# sensor_002.net
KiCad netlist of a schematic drawn in EAGLE
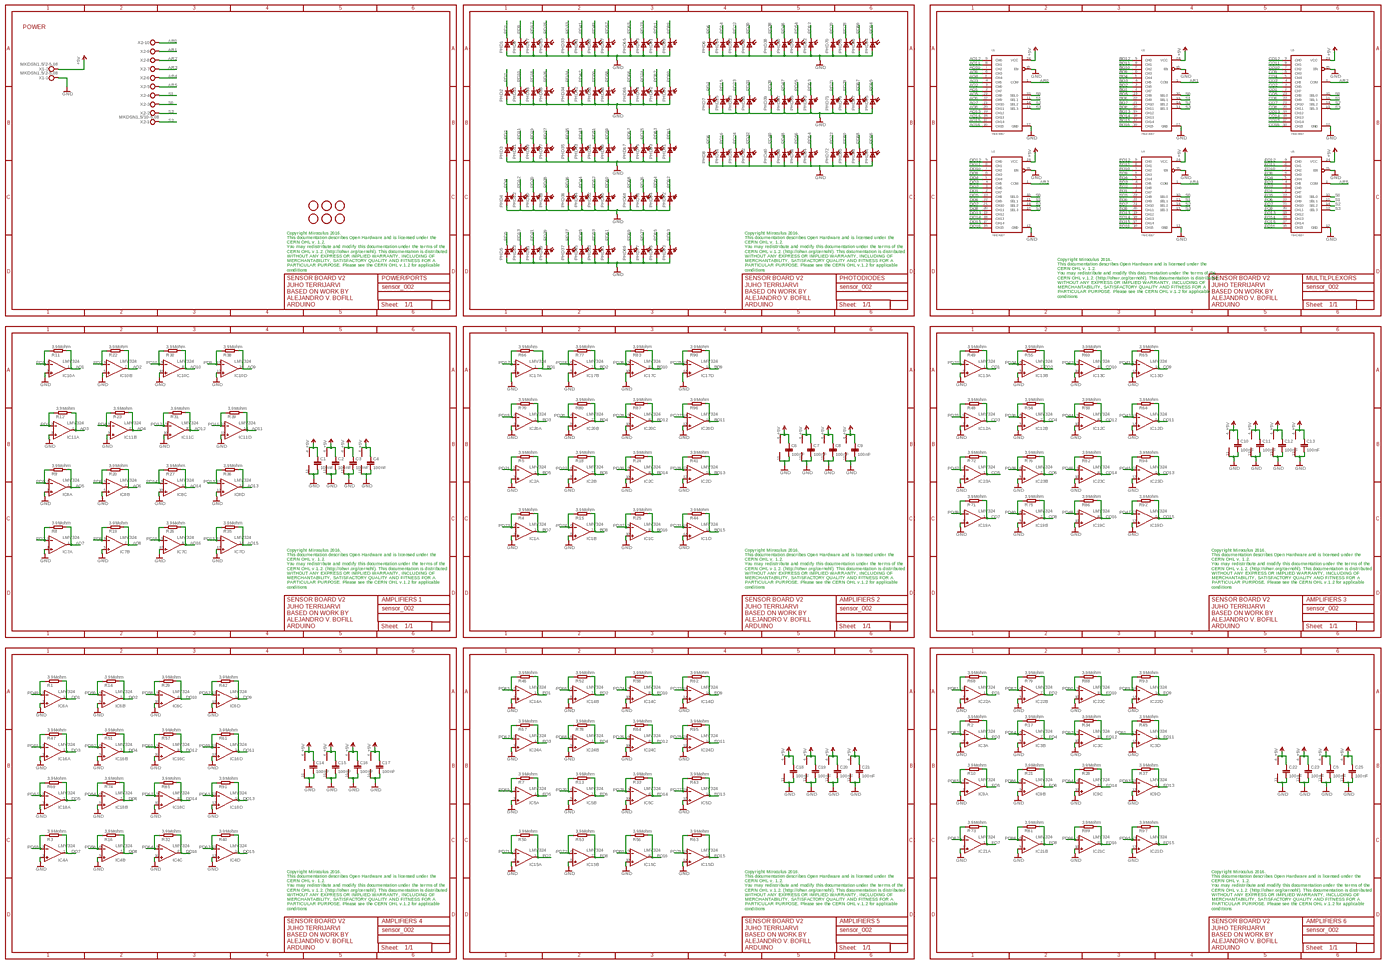
[diagram p0: schematic, sheet 1, overview]
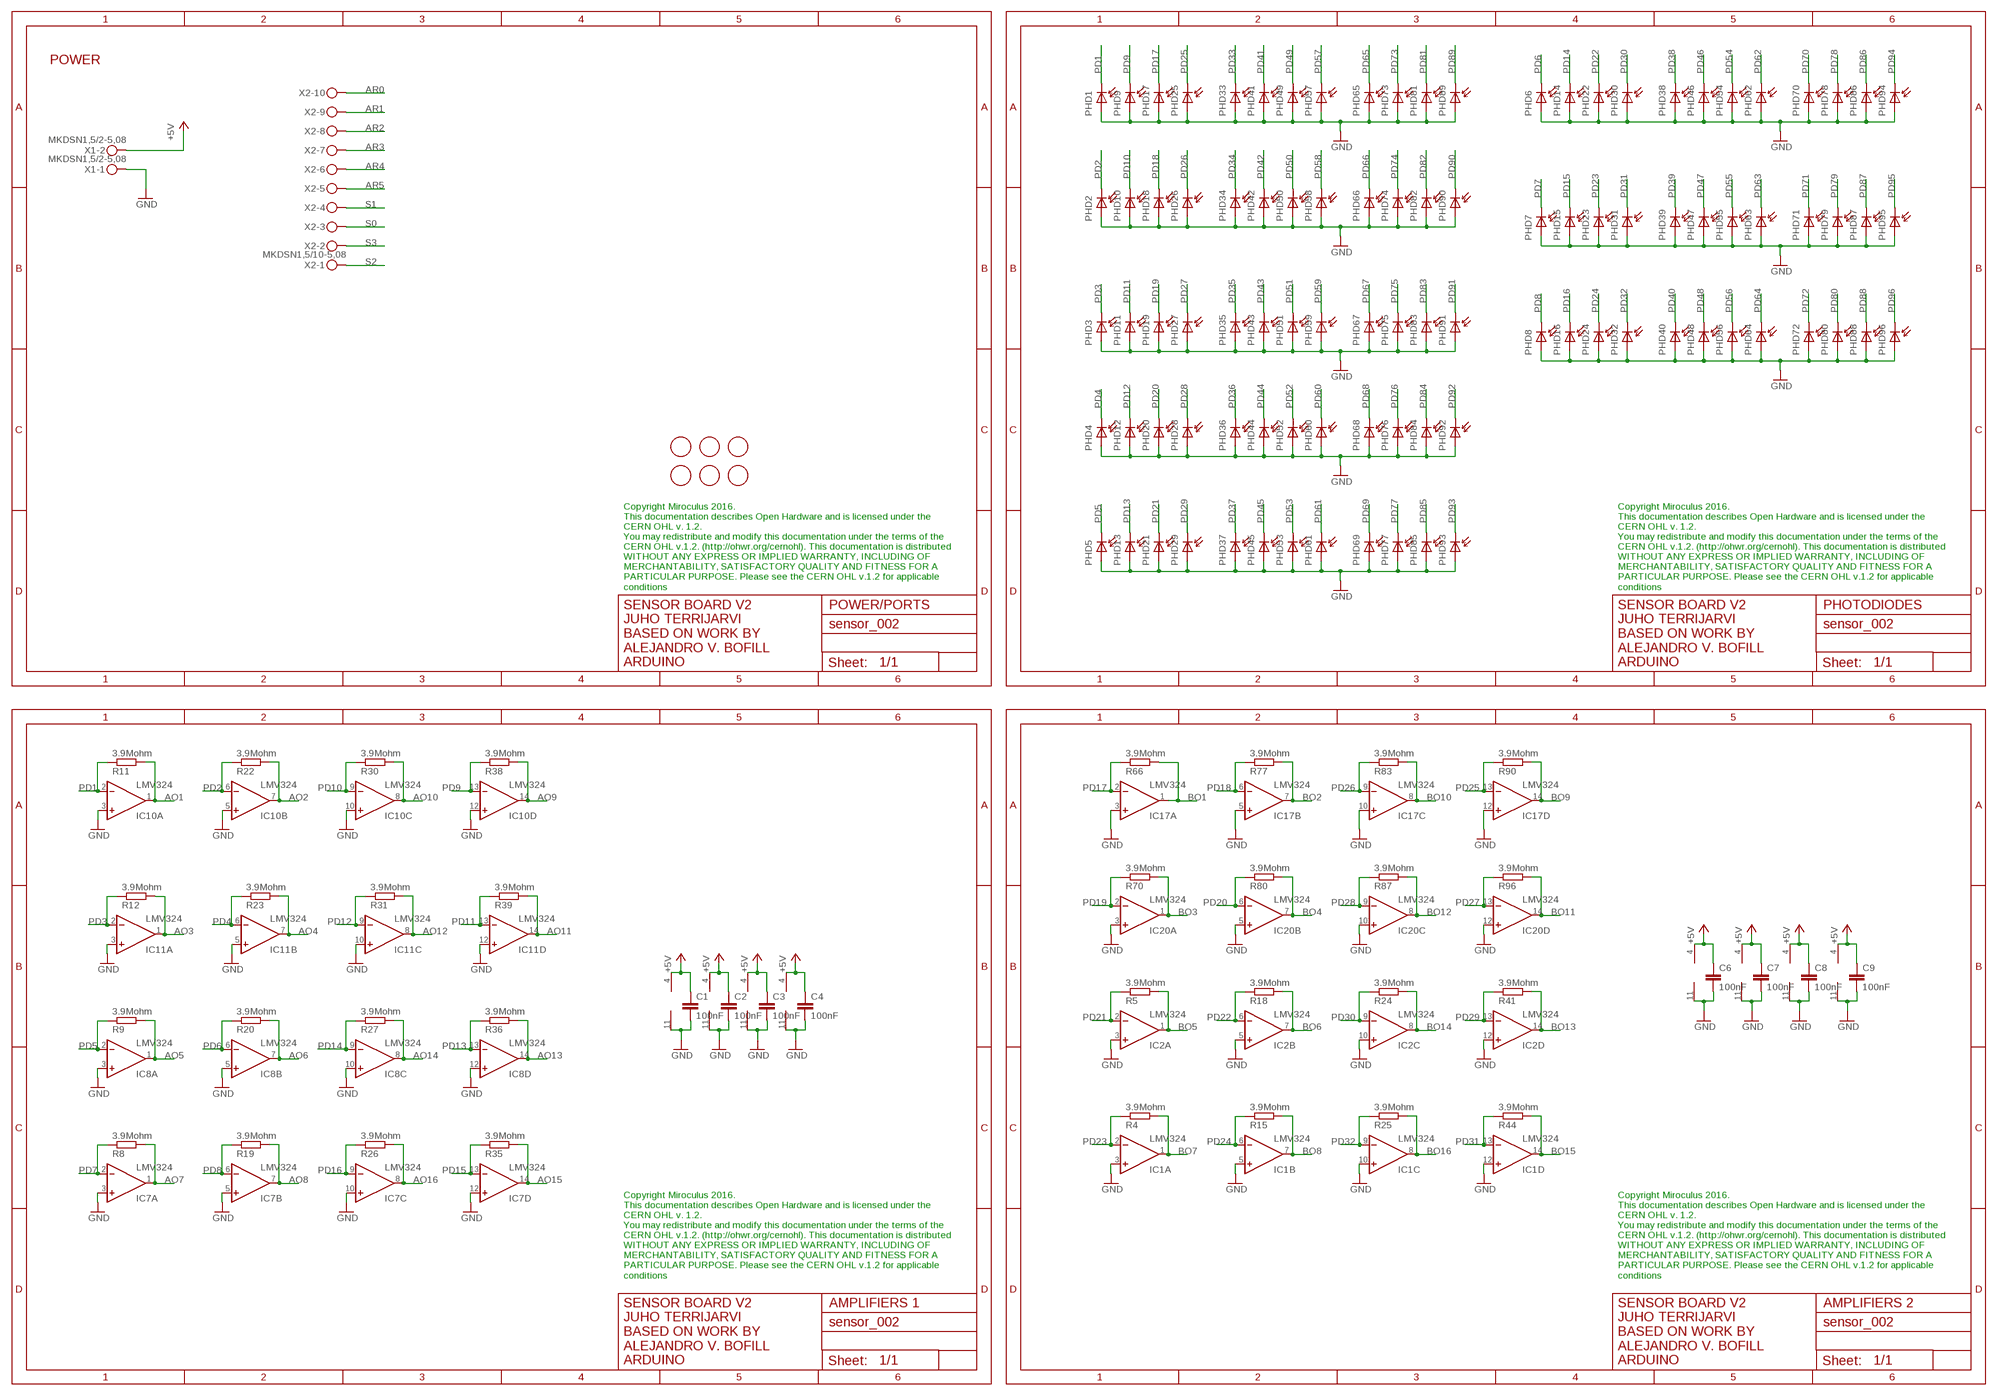
[diagram p1: schematic, sheet 1, part 1 of 4]
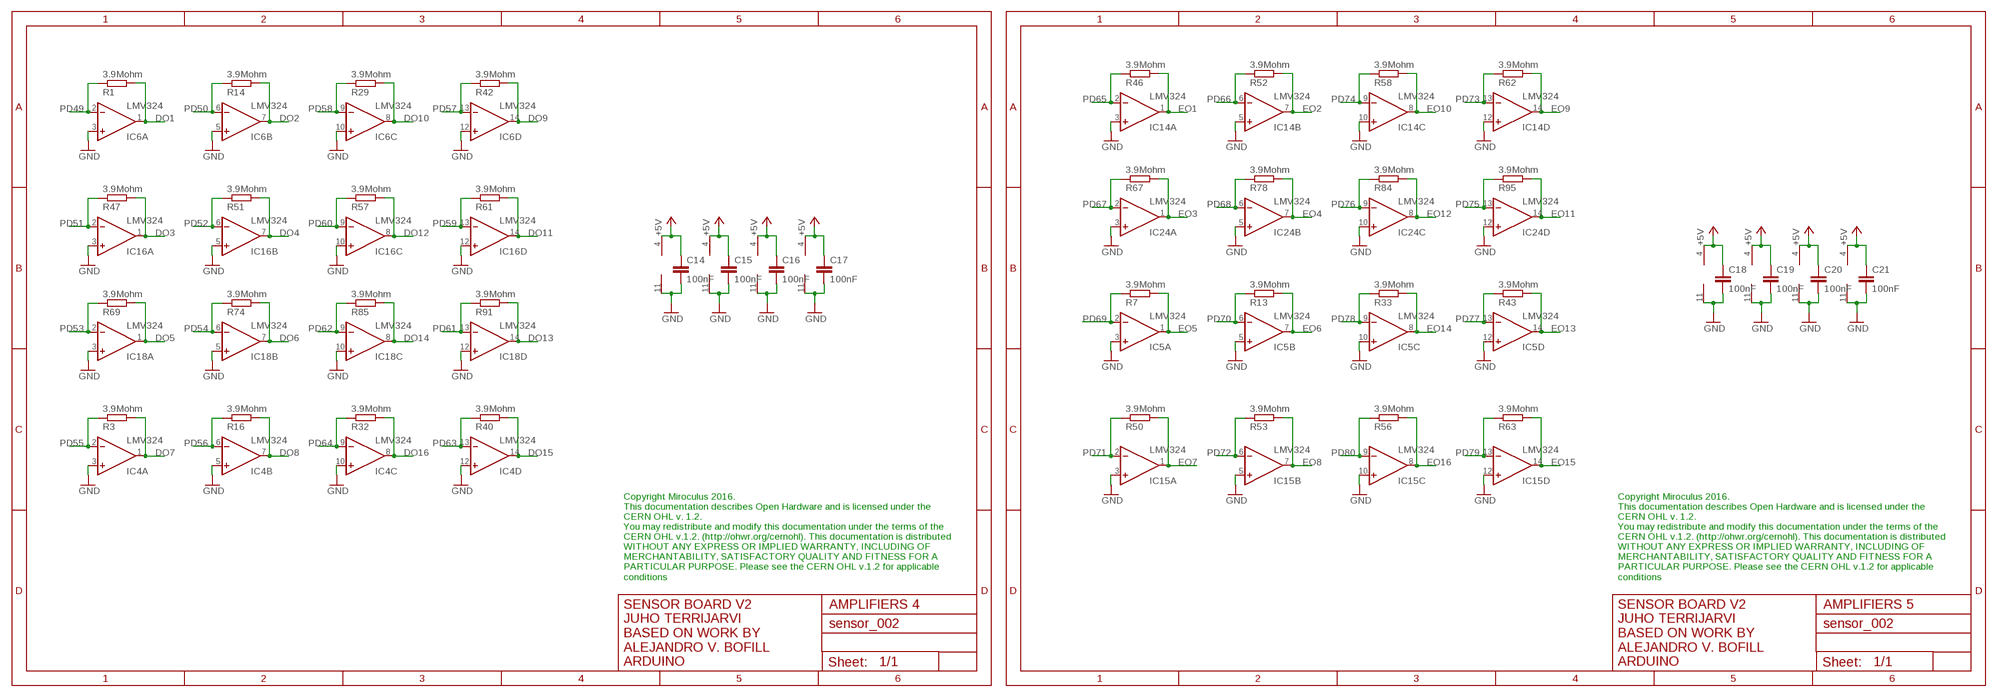
[diagram p2: schematic, sheet 1, part 2 of 4]
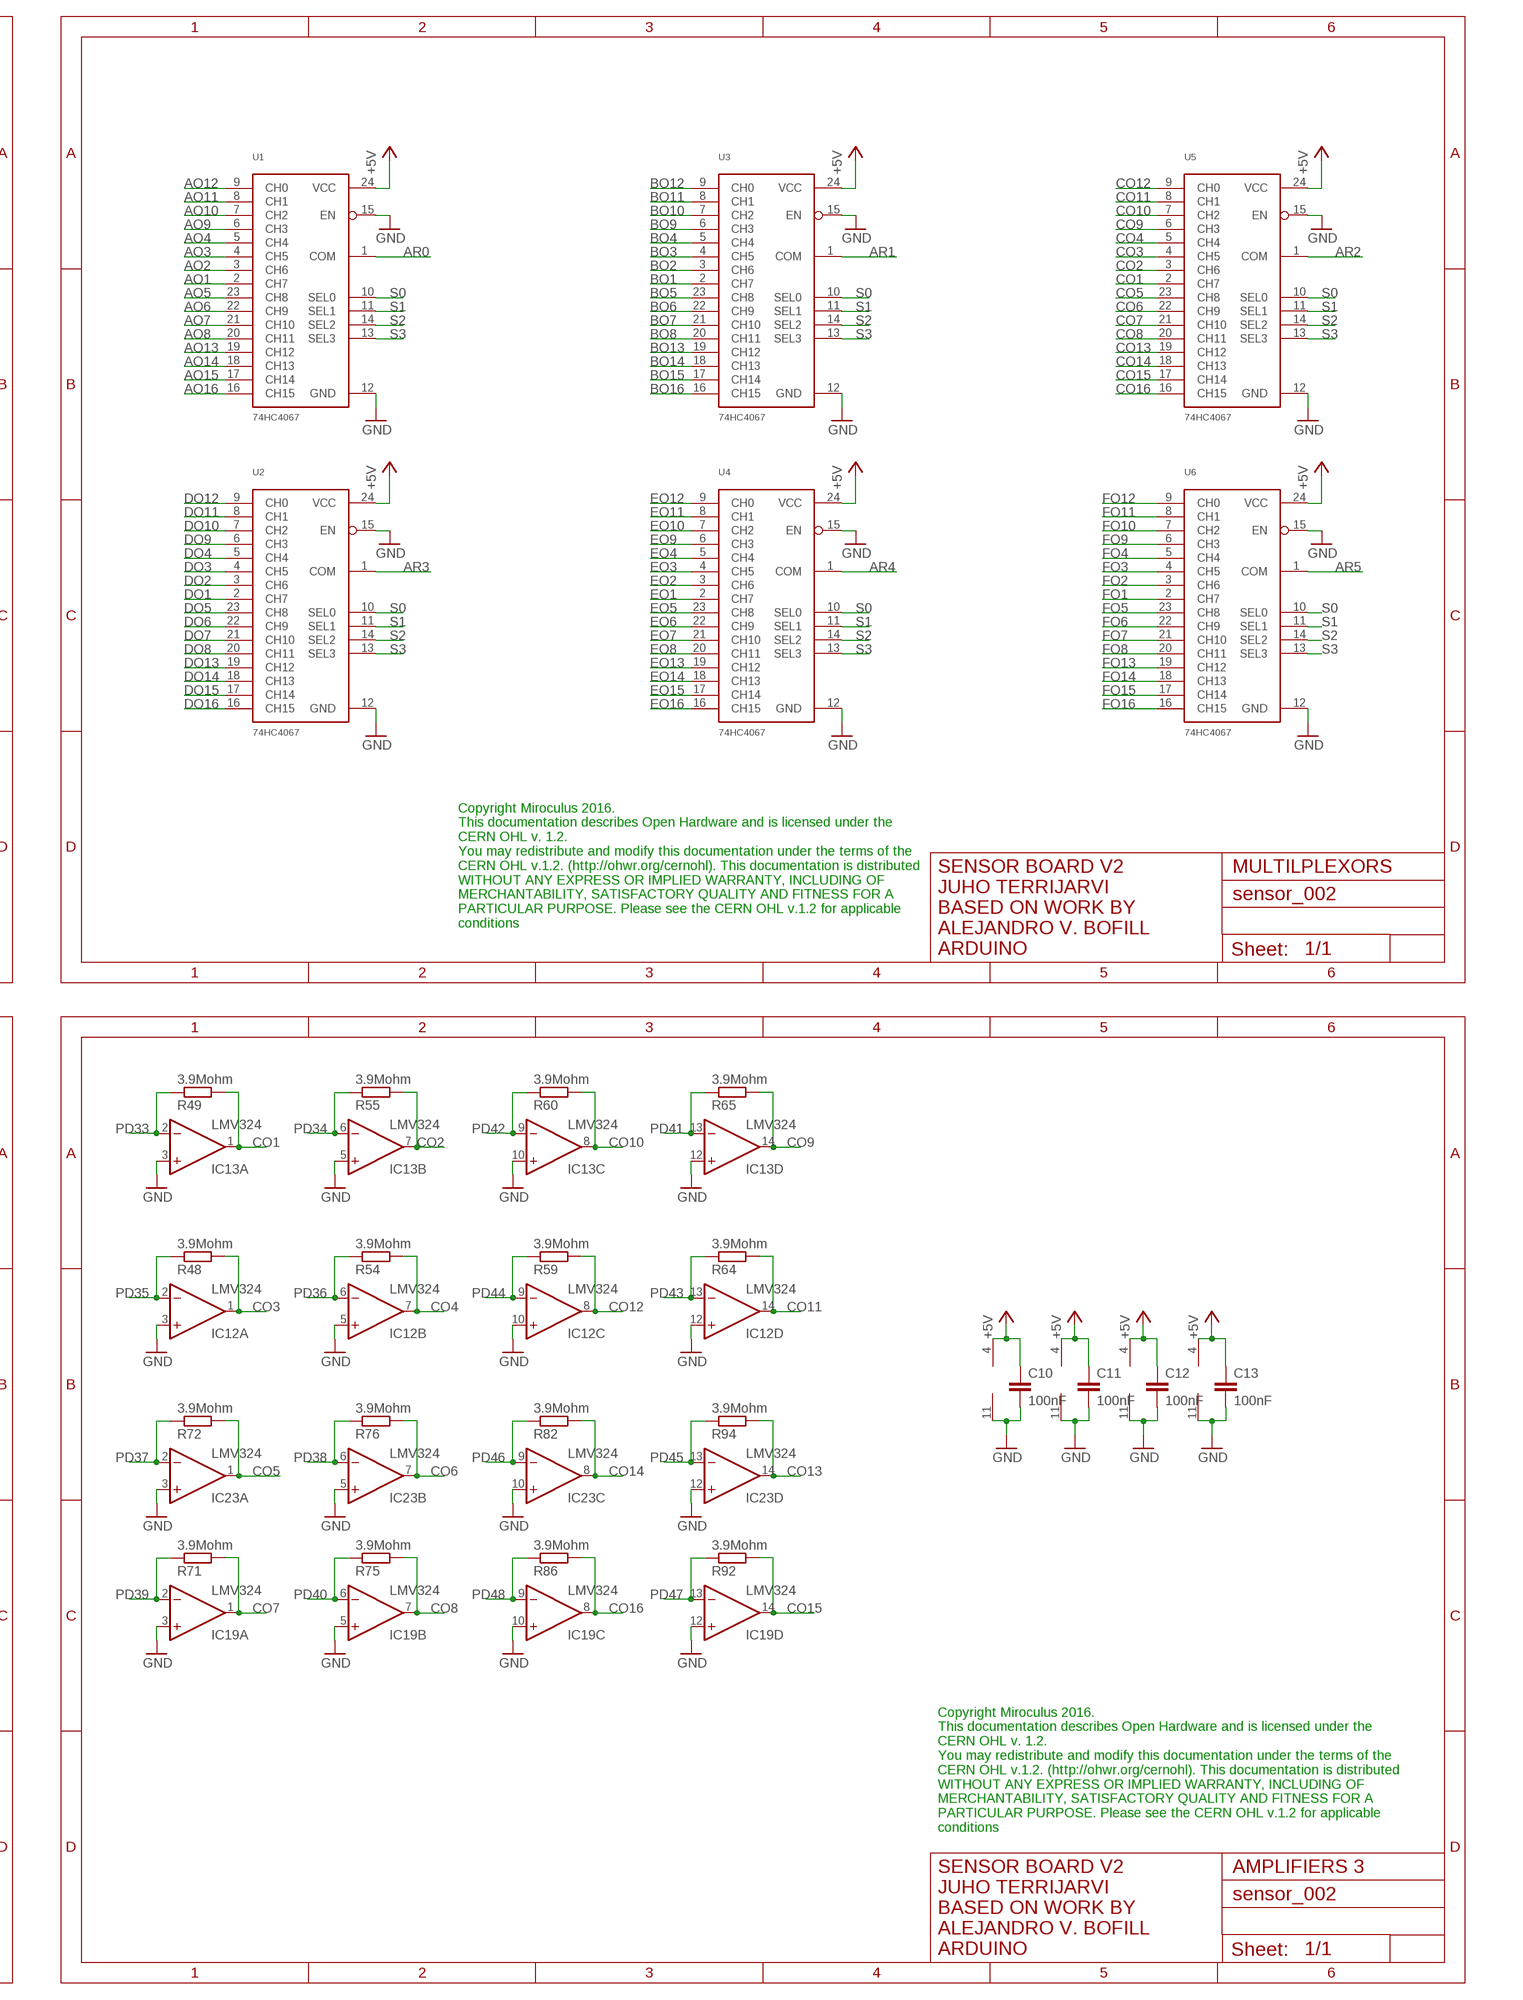
[diagram p3: schematic, sheet 1, part 3 of 4]
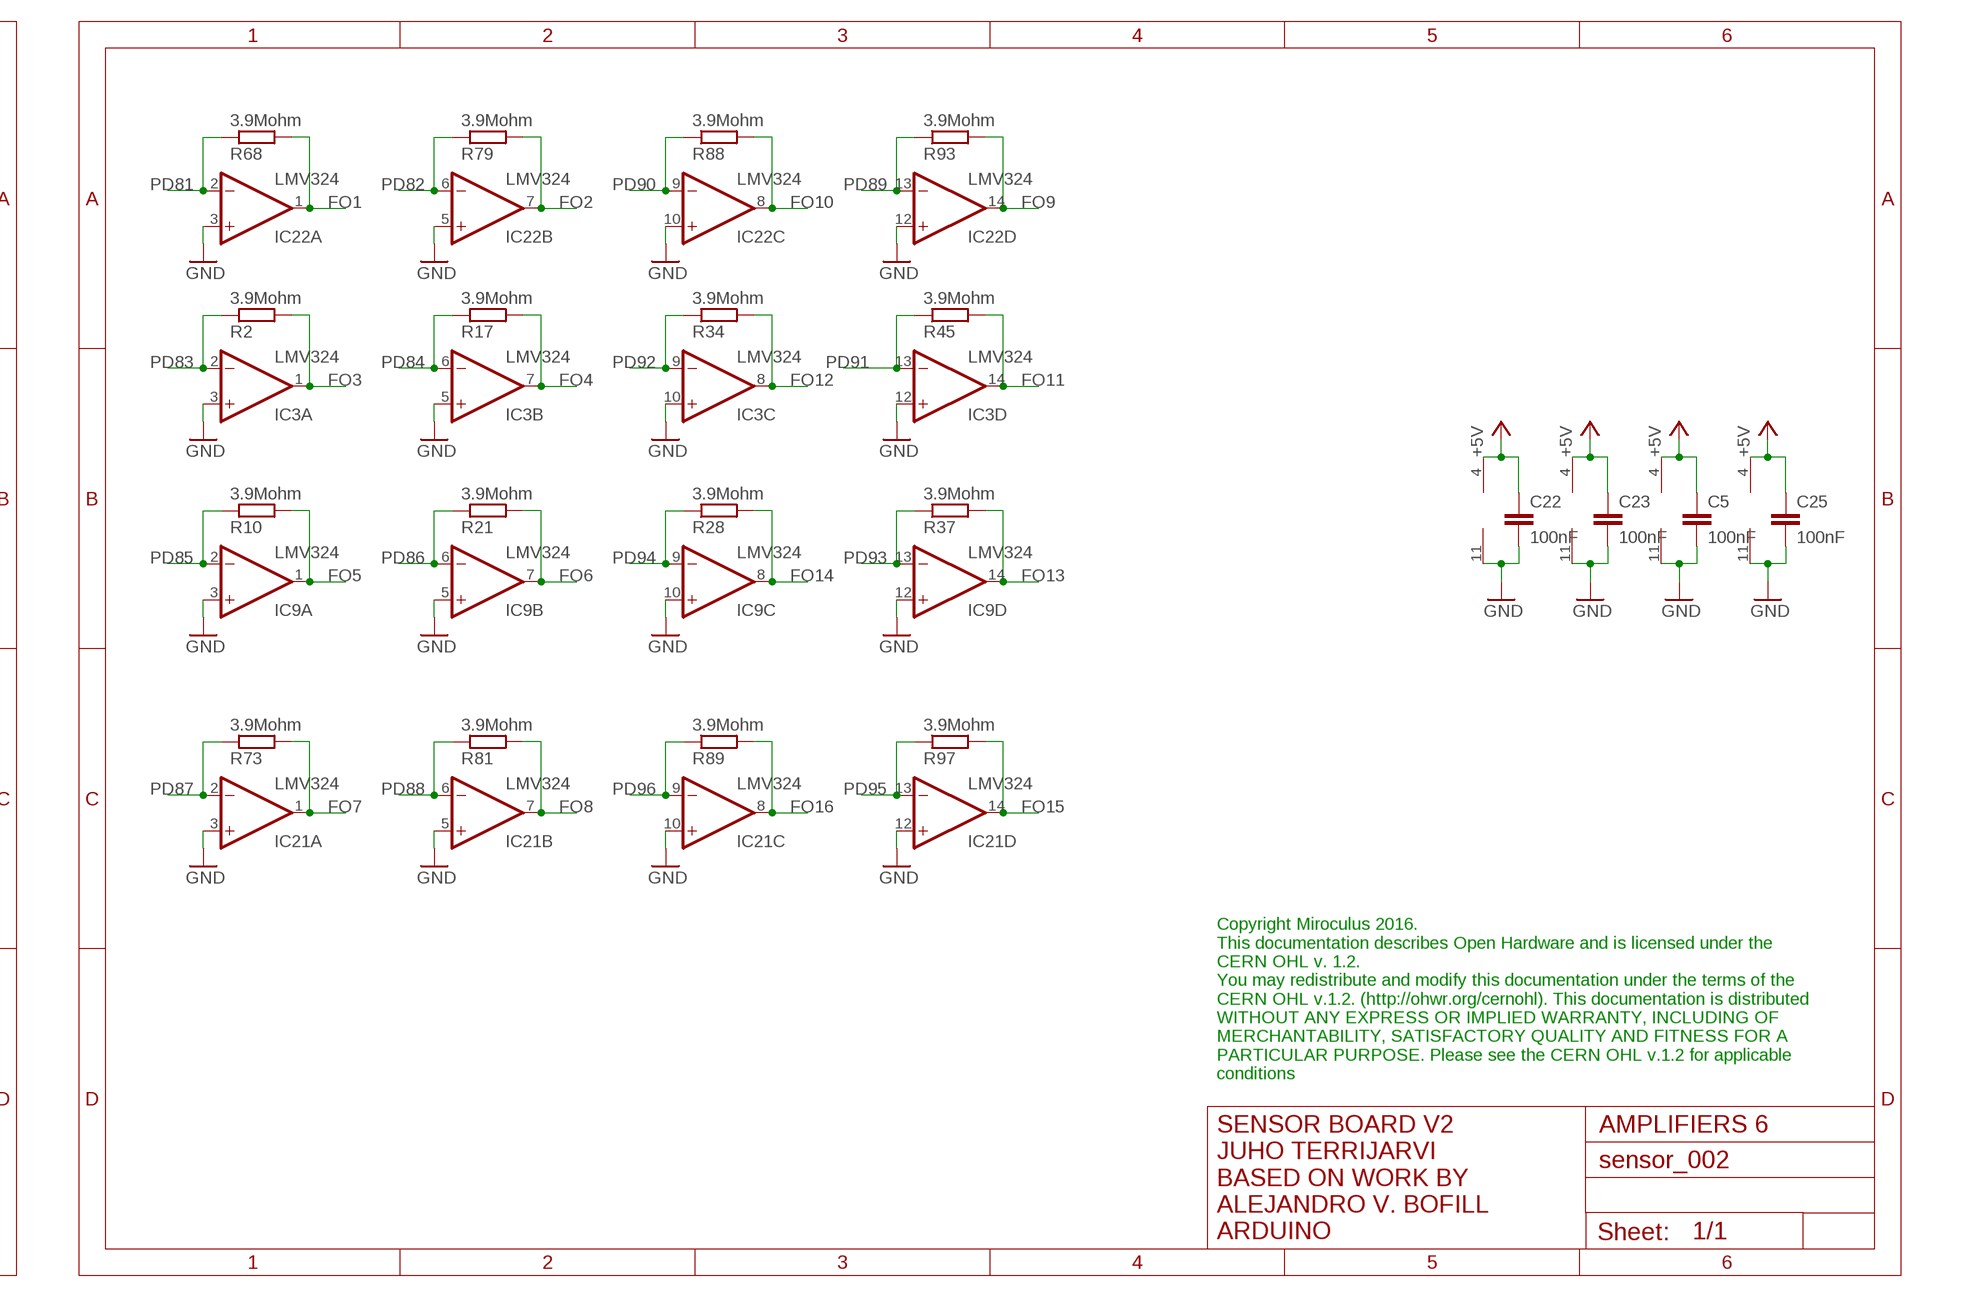
[diagram p4: schematic, sheet 1, part 4 of 4]

(export (version "E")
  (design (tool "Eeschema 10.0.6"))
  (components
    (comp (ref "C1")
      (value "100nF")
      (footprint "eagle-import:C0603")
      (libsource (lib "eagle-import") (part "C-EUC0603"))
    )
    (comp (ref "C2")
      (value "100nF")
      (footprint "eagle-import:C0603")
      (libsource (lib "eagle-import") (part "C-EUC0603"))
    )
    (comp (ref "C3")
      (value "100nF")
      (footprint "eagle-import:C0603")
      (libsource (lib "eagle-import") (part "C-EUC0603"))
    )
    (comp (ref "C4")
      (value "100nF")
      (footprint "eagle-import:C0603")
      (libsource (lib "eagle-import") (part "C-EUC0603"))
    )
    (comp (ref "C5")
      (value "100nF")
      (footprint "eagle-import:C0603")
      (libsource (lib "eagle-import") (part "C-EUC0603"))
    )
    (comp (ref "C6")
      (value "100nF")
      (footprint "eagle-import:C0603")
      (libsource (lib "eagle-import") (part "C-EUC0603"))
    )
    (comp (ref "C7")
      (value "100nF")
      (footprint "eagle-import:C0603")
      (libsource (lib "eagle-import") (part "C-EUC0603"))
    )
    (comp (ref "C8")
      (value "100nF")
      (footprint "eagle-import:C0603")
      (libsource (lib "eagle-import") (part "C-EUC0603"))
    )
    (comp (ref "C9")
      (value "100nF")
      (footprint "eagle-import:C0603")
      (libsource (lib "eagle-import") (part "C-EUC0603"))
    )
    (comp (ref "C10")
      (value "100nF")
      (footprint "eagle-import:C0603")
      (libsource (lib "eagle-import") (part "C-EUC0603"))
    )
    (comp (ref "C11")
      (value "100nF")
      (footprint "eagle-import:C0603")
      (libsource (lib "eagle-import") (part "C-EUC0603"))
    )
    (comp (ref "C12")
      (value "100nF")
      (footprint "eagle-import:C0603")
      (libsource (lib "eagle-import") (part "C-EUC0603"))
    )
    (comp (ref "C13")
      (value "100nF")
      (footprint "eagle-import:C0603")
      (libsource (lib "eagle-import") (part "C-EUC0603"))
    )
    (comp (ref "C14")
      (value "100nF")
      (footprint "eagle-import:C0603")
      (libsource (lib "eagle-import") (part "C-EUC0603"))
    )
    (comp (ref "C15")
      (value "100nF")
      (footprint "eagle-import:C0603")
      (libsource (lib "eagle-import") (part "C-EUC0603"))
    )
    (comp (ref "C16")
      (value "100nF")
      (footprint "eagle-import:C0603")
      (libsource (lib "eagle-import") (part "C-EUC0603"))
    )
    (comp (ref "C17")
      (value "100nF")
      (footprint "eagle-import:C0603")
      (libsource (lib "eagle-import") (part "C-EUC0603"))
    )
    (comp (ref "C18")
      (value "100nF")
      (footprint "eagle-import:C0603")
      (libsource (lib "eagle-import") (part "C-EUC0603"))
    )
    (comp (ref "C19")
      (value "100nF")
      (footprint "eagle-import:C0603")
      (libsource (lib "eagle-import") (part "C-EUC0603"))
    )
    (comp (ref "C20")
      (value "100nF")
      (footprint "eagle-import:C0603")
      (libsource (lib "eagle-import") (part "C-EUC0603"))
    )
    (comp (ref "C21")
      (value "100nF")
      (footprint "eagle-import:C0603")
      (libsource (lib "eagle-import") (part "C-EUC0603"))
    )
    (comp (ref "C22")
      (value "100nF")
      (footprint "eagle-import:C0603")
      (libsource (lib "eagle-import") (part "C-EUC0603"))
    )
    (comp (ref "C23")
      (value "100nF")
      (footprint "eagle-import:C0603")
      (libsource (lib "eagle-import") (part "C-EUC0603"))
    )
    (comp (ref "C25")
      (value "100nF")
      (footprint "eagle-import:C0603")
      (libsource (lib "eagle-import") (part "C-EUC0603"))
    )
    (comp (ref "FD1")
      (value "FIDUCIALMOUNT")
      (footprint "eagle-import:FIDUCIA-MOUNT")
      (libsource (lib "eagle-import") (part "FIDUCIALMOUNT"))
    )
    (comp (ref "FD2")
      (value "FIDUCIALMOUNT")
      (footprint "eagle-import:FIDUCIA-MOUNT")
      (libsource (lib "eagle-import") (part "FIDUCIALMOUNT"))
    )
    (comp (ref "FD3")
      (value "FIDUCIALMOUNT")
      (footprint "eagle-import:FIDUCIA-MOUNT")
      (libsource (lib "eagle-import") (part "FIDUCIALMOUNT"))
    )
    (comp (ref "FD4")
      (value "FIDUCIALMOUNT")
      (footprint "eagle-import:FIDUCIA-MOUNT")
      (libsource (lib "eagle-import") (part "FIDUCIALMOUNT"))
    )
    (comp (ref "FD5")
      (value "FIDUCIALMOUNT")
      (footprint "eagle-import:FIDUCIA-MOUNT")
      (libsource (lib "eagle-import") (part "FIDUCIALMOUNT"))
    )
    (comp (ref "FD6")
      (value "FIDUCIALMOUNT")
      (footprint "eagle-import:FIDUCIA-MOUNT")
      (libsource (lib "eagle-import") (part "FIDUCIALMOUNT"))
    )
    (comp (ref "IC1")
      (value "LMV324")
      (footprint "eagle-import:SO14")
      (libsource (lib "eagle-import") (part "TL074D"))
    )
    (comp (ref "IC2")
      (value "LMV324")
      (footprint "eagle-import:SO14")
      (libsource (lib "eagle-import") (part "TL074D"))
    )
    (comp (ref "IC3")
      (value "LMV324")
      (footprint "eagle-import:SO14")
      (libsource (lib "eagle-import") (part "TL074D"))
    )
    (comp (ref "IC4")
      (value "LMV324")
      (footprint "eagle-import:SO14")
      (libsource (lib "eagle-import") (part "TL074D"))
    )
    (comp (ref "IC5")
      (value "LMV324")
      (footprint "eagle-import:SO14")
      (libsource (lib "eagle-import") (part "TL074D"))
    )
    (comp (ref "IC6")
      (value "LMV324")
      (footprint "eagle-import:SO14")
      (libsource (lib "eagle-import") (part "TL074D"))
    )
    (comp (ref "IC7")
      (value "LMV324")
      (footprint "eagle-import:SO14")
      (libsource (lib "eagle-import") (part "TL074D"))
    )
    (comp (ref "IC8")
      (value "LMV324")
      (footprint "eagle-import:SO14")
      (libsource (lib "eagle-import") (part "TL074D"))
    )
    (comp (ref "IC9")
      (value "LMV324")
      (footprint "eagle-import:SO14")
      (libsource (lib "eagle-import") (part "TL074D"))
    )
    (comp (ref "IC10")
      (value "LMV324")
      (footprint "eagle-import:SO14")
      (libsource (lib "eagle-import") (part "TL074D"))
    )
    (comp (ref "IC11")
      (value "LMV324")
      (footprint "eagle-import:SO14")
      (libsource (lib "eagle-import") (part "TL074D"))
    )
    (comp (ref "IC12")
      (value "LMV324")
      (footprint "eagle-import:SO14")
      (libsource (lib "eagle-import") (part "TL074D"))
    )
    (comp (ref "IC13")
      (value "LMV324")
      (footprint "eagle-import:SO14")
      (libsource (lib "eagle-import") (part "TL074D"))
    )
    (comp (ref "IC14")
      (value "LMV324")
      (footprint "eagle-import:SO14")
      (libsource (lib "eagle-import") (part "TL074D"))
    )
    (comp (ref "IC15")
      (value "LMV324")
      (footprint "eagle-import:SO14")
      (libsource (lib "eagle-import") (part "TL074D"))
    )
    (comp (ref "IC16")
      (value "LMV324")
      (footprint "eagle-import:SO14")
      (libsource (lib "eagle-import") (part "TL074D"))
    )
    (comp (ref "IC17")
      (value "LMV324")
      (footprint "eagle-import:SO14")
      (libsource (lib "eagle-import") (part "TL074D"))
    )
    (comp (ref "IC18")
      (value "LMV324")
      (footprint "eagle-import:SO14")
      (libsource (lib "eagle-import") (part "TL074D"))
    )
    (comp (ref "IC19")
      (value "LMV324")
      (footprint "eagle-import:SO14")
      (libsource (lib "eagle-import") (part "TL074D"))
    )
    (comp (ref "IC20")
      (value "LMV324")
      (footprint "eagle-import:SO14")
      (libsource (lib "eagle-import") (part "TL074D"))
    )
    (comp (ref "IC21")
      (value "LMV324")
      (footprint "eagle-import:SO14")
      (libsource (lib "eagle-import") (part "TL074D"))
    )
    (comp (ref "IC22")
      (value "LMV324")
      (footprint "eagle-import:SO14")
      (libsource (lib "eagle-import") (part "TL074D"))
    )
    (comp (ref "IC23")
      (value "LMV324")
      (footprint "eagle-import:SO14")
      (libsource (lib "eagle-import") (part "TL074D"))
    )
    (comp (ref "IC24")
      (value "LMV324")
      (footprint "eagle-import:SO14")
      (libsource (lib "eagle-import") (part "TL074D"))
    )
    (comp (ref "PHD1")
      (value "CLS15-22C/L213G/TR8")
      (footprint "eagle-import:PD_0.2")
      (libsource (lib "eagle-import") (part "PD_0.2"))
    )
    (comp (ref "PHD2")
      (value "CLS15-22C/L213G/TR8")
      (footprint "eagle-import:PD_0.2")
      (libsource (lib "eagle-import") (part "PD_0.2"))
    )
    (comp (ref "PHD3")
      (value "CLS15-22C/L213G/TR8")
      (footprint "eagle-import:PD_0.2")
      (libsource (lib "eagle-import") (part "PD_0.2"))
    )
    (comp (ref "PHD4")
      (value "CLS15-22C/L213G/TR8")
      (footprint "eagle-import:PD_0.2")
      (libsource (lib "eagle-import") (part "PD_0.2"))
    )
    (comp (ref "PHD5")
      (value "CLS15-22C/L213G/TR8")
      (footprint "eagle-import:PD_0.2")
      (libsource (lib "eagle-import") (part "PD_0.2"))
    )
    (comp (ref "PHD6")
      (value "CLS15-22C/L213G/TR8")
      (footprint "eagle-import:PD_0.2")
      (libsource (lib "eagle-import") (part "PD_0.2"))
    )
    (comp (ref "PHD7")
      (value "CLS15-22C/L213G/TR8")
      (footprint "eagle-import:PD_0.2")
      (libsource (lib "eagle-import") (part "PD_0.2"))
    )
    (comp (ref "PHD8")
      (value "CLS15-22C/L213G/TR8")
      (footprint "eagle-import:PD_0.2")
      (libsource (lib "eagle-import") (part "PD_0.2"))
    )
    (comp (ref "PHD9")
      (value "CLS15-22C/L213G/TR8")
      (footprint "eagle-import:PD_0.2")
      (libsource (lib "eagle-import") (part "PD_0.2"))
    )
    (comp (ref "PHD10")
      (value "CLS15-22C/L213G/TR8")
      (footprint "eagle-import:PD_0.2")
      (libsource (lib "eagle-import") (part "PD_0.2"))
    )
    (comp (ref "PHD11")
      (value "CLS15-22C/L213G/TR8")
      (footprint "eagle-import:PD_0.2")
      (libsource (lib "eagle-import") (part "PD_0.2"))
    )
    (comp (ref "PHD12")
      (value "CLS15-22C/L213G/TR8")
      (footprint "eagle-import:PD_0.2")
      (libsource (lib "eagle-import") (part "PD_0.2"))
    )
    (comp (ref "PHD13")
      (value "CLS15-22C/L213G/TR8")
      (footprint "eagle-import:PD_0.2")
      (libsource (lib "eagle-import") (part "PD_0.2"))
    )
    (comp (ref "PHD14")
      (value "CLS15-22C/L213G/TR8")
      (footprint "eagle-import:PD_0.2")
      (libsource (lib "eagle-import") (part "PD_0.2"))
    )
    (comp (ref "PHD15")
      (value "CLS15-22C/L213G/TR8")
      (footprint "eagle-import:PD_0.2")
      (libsource (lib "eagle-import") (part "PD_0.2"))
    )
    (comp (ref "PHD16")
      (value "CLS15-22C/L213G/TR8")
      (footprint "eagle-import:PD_0.2")
      (libsource (lib "eagle-import") (part "PD_0.2"))
    )
    (comp (ref "PHD17")
      (value "CLS15-22C/L213G/TR8")
      (footprint "eagle-import:PD_0.2")
      (libsource (lib "eagle-import") (part "PD_0.2"))
    )
    (comp (ref "PHD18")
      (value "CLS15-22C/L213G/TR8")
      (footprint "eagle-import:PD_0.2")
      (libsource (lib "eagle-import") (part "PD_0.2"))
    )
    (comp (ref "PHD19")
      (value "CLS15-22C/L213G/TR8")
      (footprint "eagle-import:PD_0.2")
      (libsource (lib "eagle-import") (part "PD_0.2"))
    )
    (comp (ref "PHD20")
      (value "CLS15-22C/L213G/TR8")
      (footprint "eagle-import:PD_0.2")
      (libsource (lib "eagle-import") (part "PD_0.2"))
    )
    (comp (ref "PHD21")
      (value "CLS15-22C/L213G/TR8")
      (footprint "eagle-import:PD_0.2")
      (libsource (lib "eagle-import") (part "PD_0.2"))
    )
    (comp (ref "PHD22")
      (value "CLS15-22C/L213G/TR8")
      (footprint "eagle-import:PD_0.2")
      (libsource (lib "eagle-import") (part "PD_0.2"))
    )
    (comp (ref "PHD23")
      (value "CLS15-22C/L213G/TR8")
      (footprint "eagle-import:PD_0.2")
      (libsource (lib "eagle-import") (part "PD_0.2"))
    )
    (comp (ref "PHD24")
      (value "CLS15-22C/L213G/TR8")
      (footprint "eagle-import:PD_0.2")
      (libsource (lib "eagle-import") (part "PD_0.2"))
    )
    (comp (ref "PHD25")
      (value "CLS15-22C/L213G/TR8")
      (footprint "eagle-import:PD_0.2")
      (libsource (lib "eagle-import") (part "PD_0.2"))
    )
    (comp (ref "PHD26")
      (value "CLS15-22C/L213G/TR8")
      (footprint "eagle-import:PD_0.2")
      (libsource (lib "eagle-import") (part "PD_0.2"))
    )
    (comp (ref "PHD27")
      (value "CLS15-22C/L213G/TR8")
      (footprint "eagle-import:PD_0.2")
      (libsource (lib "eagle-import") (part "PD_0.2"))
    )
    (comp (ref "PHD28")
      (value "CLS15-22C/L213G/TR8")
      (footprint "eagle-import:PD_0.2")
      (libsource (lib "eagle-import") (part "PD_0.2"))
    )
    (comp (ref "PHD29")
      (value "CLS15-22C/L213G/TR8")
      (footprint "eagle-import:PD_0.2")
      (libsource (lib "eagle-import") (part "PD_0.2"))
    )
    (comp (ref "PHD30")
      (value "CLS15-22C/L213G/TR8")
      (footprint "eagle-import:PD_0.2")
      (libsource (lib "eagle-import") (part "PD_0.2"))
    )
    (comp (ref "PHD31")
      (value "CLS15-22C/L213G/TR8")
      (footprint "eagle-import:PD_0.2")
      (libsource (lib "eagle-import") (part "PD_0.2"))
    )
    (comp (ref "PHD32")
      (value "CLS15-22C/L213G/TR8")
      (footprint "eagle-import:PD_0.2")
      (libsource (lib "eagle-import") (part "PD_0.2"))
    )
    (comp (ref "PHD33")
      (value "CLS15-22C/L213G/TR8")
      (footprint "eagle-import:PD_0.2")
      (libsource (lib "eagle-import") (part "PD_0.2"))
    )
    (comp (ref "PHD34")
      (value "CLS15-22C/L213G/TR8")
      (footprint "eagle-import:PD_0.2")
      (libsource (lib "eagle-import") (part "PD_0.2"))
    )
    (comp (ref "PHD35")
      (value "CLS15-22C/L213G/TR8")
      (footprint "eagle-import:PD_0.2")
      (libsource (lib "eagle-import") (part "PD_0.2"))
    )
    (comp (ref "PHD36")
      (value "CLS15-22C/L213G/TR8")
      (footprint "eagle-import:PD_0.2")
      (libsource (lib "eagle-import") (part "PD_0.2"))
    )
    (comp (ref "PHD37")
      (value "CLS15-22C/L213G/TR8")
      (footprint "eagle-import:PD_0.2")
      (libsource (lib "eagle-import") (part "PD_0.2"))
    )
    (comp (ref "PHD38")
      (value "CLS15-22C/L213G/TR8")
      (footprint "eagle-import:PD_0.2")
      (libsource (lib "eagle-import") (part "PD_0.2"))
    )
    (comp (ref "PHD39")
      (value "CLS15-22C/L213G/TR8")
      (footprint "eagle-import:PD_0.2")
      (libsource (lib "eagle-import") (part "PD_0.2"))
    )
    (comp (ref "PHD40")
      (value "CLS15-22C/L213G/TR8")
      (footprint "eagle-import:PD_0.2")
      (libsource (lib "eagle-import") (part "PD_0.2"))
    )
    (comp (ref "PHD41")
      (value "CLS15-22C/L213G/TR8")
      (footprint "eagle-import:PD_0.2")
      (libsource (lib "eagle-import") (part "PD_0.2"))
    )
    (comp (ref "PHD42")
      (value "CLS15-22C/L213G/TR8")
      (footprint "eagle-import:PD_0.2")
      (libsource (lib "eagle-import") (part "PD_0.2"))
    )
    (comp (ref "PHD43")
      (value "CLS15-22C/L213G/TR8")
      (footprint "eagle-import:PD_0.2")
      (libsource (lib "eagle-import") (part "PD_0.2"))
    )
    (comp (ref "PHD44")
      (value "CLS15-22C/L213G/TR8")
      (footprint "eagle-import:PD_0.2")
      (libsource (lib "eagle-import") (part "PD_0.2"))
    )
    (comp (ref "PHD45")
      (value "CLS15-22C/L213G/TR8")
      (footprint "eagle-import:PD_0.2")
      (libsource (lib "eagle-import") (part "PD_0.2"))
    )
    (comp (ref "PHD46")
      (value "CLS15-22C/L213G/TR8")
      (footprint "eagle-import:PD_0.2")
      (libsource (lib "eagle-import") (part "PD_0.2"))
    )
    (comp (ref "PHD47")
      (value "CLS15-22C/L213G/TR8")
      (footprint "eagle-import:PD_0.2")
      (libsource (lib "eagle-import") (part "PD_0.2"))
    )
    (comp (ref "PHD48")
      (value "CLS15-22C/L213G/TR8")
      (footprint "eagle-import:PD_0.2")
      (libsource (lib "eagle-import") (part "PD_0.2"))
    )
    (comp (ref "PHD49")
      (value "CLS15-22C/L213G/TR8")
      (footprint "eagle-import:PD_0.2")
      (libsource (lib "eagle-import") (part "PD_0.2"))
    )
    (comp (ref "PHD50")
      (value "CLS15-22C/L213G/TR8")
      (footprint "eagle-import:PD_0.2")
      (libsource (lib "eagle-import") (part "PD_0.2"))
    )
    (comp (ref "PHD51")
      (value "CLS15-22C/L213G/TR8")
      (footprint "eagle-import:PD_0.2")
      (libsource (lib "eagle-import") (part "PD_0.2"))
    )
    (comp (ref "PHD52")
      (value "CLS15-22C/L213G/TR8")
      (footprint "eagle-import:PD_0.2")
      (libsource (lib "eagle-import") (part "PD_0.2"))
    )
    (comp (ref "PHD53")
      (value "CLS15-22C/L213G/TR8")
      (footprint "eagle-import:PD_0.2")
      (libsource (lib "eagle-import") (part "PD_0.2"))
    )
    (comp (ref "PHD54")
      (value "CLS15-22C/L213G/TR8")
      (footprint "eagle-import:PD_0.2")
      (libsource (lib "eagle-import") (part "PD_0.2"))
    )
    (comp (ref "PHD55")
      (value "CLS15-22C/L213G/TR8")
      (footprint "eagle-import:PD_0.2")
      (libsource (lib "eagle-import") (part "PD_0.2"))
    )
    (comp (ref "PHD56")
      (value "CLS15-22C/L213G/TR8")
      (footprint "eagle-import:PD_0.2")
      (libsource (lib "eagle-import") (part "PD_0.2"))
    )
    (comp (ref "PHD57")
      (value "CLS15-22C/L213G/TR8")
      (footprint "eagle-import:PD_0.2")
      (libsource (lib "eagle-import") (part "PD_0.2"))
    )
    (comp (ref "PHD58")
      (value "CLS15-22C/L213G/TR8")
      (footprint "eagle-import:PD_0.2")
      (libsource (lib "eagle-import") (part "PD_0.2"))
    )
    (comp (ref "PHD59")
      (value "CLS15-22C/L213G/TR8")
      (footprint "eagle-import:PD_0.2")
      (libsource (lib "eagle-import") (part "PD_0.2"))
    )
    (comp (ref "PHD60")
      (value "CLS15-22C/L213G/TR8")
      (footprint "eagle-import:PD_0.2")
      (libsource (lib "eagle-import") (part "PD_0.2"))
    )
    (comp (ref "PHD61")
      (value "CLS15-22C/L213G/TR8")
      (footprint "eagle-import:PD_0.2")
      (libsource (lib "eagle-import") (part "PD_0.2"))
    )
    (comp (ref "PHD62")
      (value "CLS15-22C/L213G/TR8")
      (footprint "eagle-import:PD_0.2")
      (libsource (lib "eagle-import") (part "PD_0.2"))
    )
    (comp (ref "PHD63")
      (value "CLS15-22C/L213G/TR8")
      (footprint "eagle-import:PD_0.2")
      (libsource (lib "eagle-import") (part "PD_0.2"))
    )
    (comp (ref "PHD64")
      (value "CLS15-22C/L213G/TR8")
      (footprint "eagle-import:PD_0.2")
      (libsource (lib "eagle-import") (part "PD_0.2"))
    )
    (comp (ref "PHD65")
      (value "CLS15-22C/L213G/TR8")
      (footprint "eagle-import:PD_0.2")
      (libsource (lib "eagle-import") (part "PD_0.2"))
    )
    (comp (ref "PHD66")
      (value "CLS15-22C/L213G/TR8")
      (footprint "eagle-import:PD_0.2")
      (libsource (lib "eagle-import") (part "PD_0.2"))
    )
    (comp (ref "PHD67")
      (value "CLS15-22C/L213G/TR8")
      (footprint "eagle-import:PD_0.2")
      (libsource (lib "eagle-import") (part "PD_0.2"))
    )
    (comp (ref "PHD68")
      (value "CLS15-22C/L213G/TR8")
      (footprint "eagle-import:PD_0.2")
      (libsource (lib "eagle-import") (part "PD_0.2"))
    )
    (comp (ref "PHD69")
      (value "CLS15-22C/L213G/TR8")
      (footprint "eagle-import:PD_0.2")
      (libsource (lib "eagle-import") (part "PD_0.2"))
    )
    (comp (ref "PHD70")
      (value "CLS15-22C/L213G/TR8")
      (footprint "eagle-import:PD_0.2")
      (libsource (lib "eagle-import") (part "PD_0.2"))
    )
    (comp (ref "PHD71")
      (value "CLS15-22C/L213G/TR8")
      (footprint "eagle-import:PD_0.2")
      (libsource (lib "eagle-import") (part "PD_0.2"))
    )
    (comp (ref "PHD72")
      (value "CLS15-22C/L213G/TR8")
      (footprint "eagle-import:PD_0.2")
      (libsource (lib "eagle-import") (part "PD_0.2"))
    )
    (comp (ref "PHD73")
      (value "CLS15-22C/L213G/TR8")
      (footprint "eagle-import:PD_0.2")
      (libsource (lib "eagle-import") (part "PD_0.2"))
    )
    (comp (ref "PHD74")
      (value "CLS15-22C/L213G/TR8")
      (footprint "eagle-import:PD_0.2")
      (libsource (lib "eagle-import") (part "PD_0.2"))
    )
    (comp (ref "PHD75")
      (value "CLS15-22C/L213G/TR8")
      (footprint "eagle-import:PD_0.2")
      (libsource (lib "eagle-import") (part "PD_0.2"))
    )
    (comp (ref "PHD76")
      (value "CLS15-22C/L213G/TR8")
      (footprint "eagle-import:PD_0.2")
      (libsource (lib "eagle-import") (part "PD_0.2"))
    )
    (comp (ref "PHD77")
      (value "CLS15-22C/L213G/TR8")
      (footprint "eagle-import:PD_0.2")
      (libsource (lib "eagle-import") (part "PD_0.2"))
    )
    (comp (ref "PHD78")
      (value "CLS15-22C/L213G/TR8")
      (footprint "eagle-import:PD_0.2")
      (libsource (lib "eagle-import") (part "PD_0.2"))
    )
    (comp (ref "PHD79")
      (value "CLS15-22C/L213G/TR8")
      (footprint "eagle-import:PD_0.2")
      (libsource (lib "eagle-import") (part "PD_0.2"))
    )
    (comp (ref "PHD80")
      (value "CLS15-22C/L213G/TR8")
      (footprint "eagle-import:PD_0.2")
      (libsource (lib "eagle-import") (part "PD_0.2"))
    )
    (comp (ref "PHD81")
      (value "CLS15-22C/L213G/TR8")
      (footprint "eagle-import:PD_0.2")
      (libsource (lib "eagle-import") (part "PD_0.2"))
    )
    (comp (ref "PHD82")
      (value "CLS15-22C/L213G/TR8")
      (footprint "eagle-import:PD_0.2")
      (libsource (lib "eagle-import") (part "PD_0.2"))
    )
    (comp (ref "PHD83")
      (value "CLS15-22C/L213G/TR8")
      (footprint "eagle-import:PD_0.2")
      (libsource (lib "eagle-import") (part "PD_0.2"))
    )
    (comp (ref "PHD84")
      (value "CLS15-22C/L213G/TR8")
      (footprint "eagle-import:PD_0.2")
      (libsource (lib "eagle-import") (part "PD_0.2"))
    )
    (comp (ref "PHD85")
      (value "CLS15-22C/L213G/TR8")
      (footprint "eagle-import:PD_0.2")
      (libsource (lib "eagle-import") (part "PD_0.2"))
    )
    (comp (ref "PHD86")
      (value "CLS15-22C/L213G/TR8")
      (footprint "eagle-import:PD_0.2")
      (libsource (lib "eagle-import") (part "PD_0.2"))
    )
    (comp (ref "PHD87")
      (value "CLS15-22C/L213G/TR8")
      (footprint "eagle-import:PD_0.2")
      (libsource (lib "eagle-import") (part "PD_0.2"))
    )
    (comp (ref "PHD88")
      (value "CLS15-22C/L213G/TR8")
      (footprint "eagle-import:PD_0.2")
      (libsource (lib "eagle-import") (part "PD_0.2"))
    )
    (comp (ref "PHD89")
      (value "CLS15-22C/L213G/TR8")
      (footprint "eagle-import:PD_0.2")
      (libsource (lib "eagle-import") (part "PD_0.2"))
    )
    (comp (ref "PHD90")
      (value "CLS15-22C/L213G/TR8")
      (footprint "eagle-import:PD_0.2")
      (libsource (lib "eagle-import") (part "PD_0.2"))
    )
    (comp (ref "PHD91")
      (value "CLS15-22C/L213G/TR8")
      (footprint "eagle-import:PD_0.2")
      (libsource (lib "eagle-import") (part "PD_0.2"))
    )
    (comp (ref "PHD92")
      (value "CLS15-22C/L213G/TR8")
      (footprint "eagle-import:PD_0.2")
      (libsource (lib "eagle-import") (part "PD_0.2"))
    )
    (comp (ref "PHD93")
      (value "CLS15-22C/L213G/TR8")
      (footprint "eagle-import:PD_0.2")
      (libsource (lib "eagle-import") (part "PD_0.2"))
    )
    (comp (ref "PHD94")
      (value "CLS15-22C/L213G/TR8")
      (footprint "eagle-import:PD_0.2")
      (libsource (lib "eagle-import") (part "PD_0.2"))
    )
    (comp (ref "PHD95")
      (value "CLS15-22C/L213G/TR8")
      (footprint "eagle-import:PD_0.2")
      (libsource (lib "eagle-import") (part "PD_0.2"))
    )
    (comp (ref "PHD96")
      (value "CLS15-22C/L213G/TR8")
      (footprint "eagle-import:PD_0.2")
      (libsource (lib "eagle-import") (part "PD_0.2"))
    )
    (comp (ref "R1")
      (value "3.9Mohm")
      (footprint "eagle-import:R0603")
      (libsource (lib "eagle-import") (part "R-EU_R0603"))
    )
    (comp (ref "R2")
      (value "3.9Mohm")
      (footprint "eagle-import:R0603")
      (libsource (lib "eagle-import") (part "R-EU_R0603"))
    )
    (comp (ref "R3")
      (value "3.9Mohm")
      (footprint "eagle-import:R0603")
      (libsource (lib "eagle-import") (part "R-EU_R0603"))
    )
    (comp (ref "R4")
      (value "3.9Mohm")
      (footprint "eagle-import:R0603")
      (libsource (lib "eagle-import") (part "R-EU_R0603"))
    )
    (comp (ref "R5")
      (value "3.9Mohm")
      (footprint "eagle-import:R0603")
      (libsource (lib "eagle-import") (part "R-EU_R0603"))
    )
    (comp (ref "R7")
      (value "3.9Mohm")
      (footprint "eagle-import:R0603")
      (libsource (lib "eagle-import") (part "R-EU_R0603"))
    )
    (comp (ref "R8")
      (value "3.9Mohm")
      (footprint "eagle-import:R0603")
      (libsource (lib "eagle-import") (part "R-EU_R0603"))
    )
    (comp (ref "R9")
      (value "3.9Mohm")
      (footprint "eagle-import:R0603")
      (libsource (lib "eagle-import") (part "R-EU_R0603"))
    )
    (comp (ref "R10")
      (value "3.9Mohm")
      (footprint "eagle-import:R0603")
      (libsource (lib "eagle-import") (part "R-EU_R0603"))
    )
    (comp (ref "R11")
      (value "3.9Mohm")
      (footprint "eagle-import:R0603")
      (libsource (lib "eagle-import") (part "R-EU_R0603"))
    )
    (comp (ref "R12")
      (value "3.9Mohm")
      (footprint "eagle-import:R0603")
      (libsource (lib "eagle-import") (part "R-EU_R0603"))
    )
    (comp (ref "R13")
      (value "3.9Mohm")
      (footprint "eagle-import:R0603")
      (libsource (lib "eagle-import") (part "R-EU_R0603"))
    )
    (comp (ref "R14")
      (value "3.9Mohm")
      (footprint "eagle-import:R0603")
      (libsource (lib "eagle-import") (part "R-EU_R0603"))
    )
    (comp (ref "R15")
      (value "3.9Mohm")
      (footprint "eagle-import:R0603")
      (libsource (lib "eagle-import") (part "R-EU_R0603"))
    )
    (comp (ref "R16")
      (value "3.9Mohm")
      (footprint "eagle-import:R0603")
      (libsource (lib "eagle-import") (part "R-EU_R0603"))
    )
    (comp (ref "R17")
      (value "3.9Mohm")
      (footprint "eagle-import:R0603")
      (libsource (lib "eagle-import") (part "R-EU_R0603"))
    )
    (comp (ref "R18")
      (value "3.9Mohm")
      (footprint "eagle-import:R0603")
      (libsource (lib "eagle-import") (part "R-EU_R0603"))
    )
    (comp (ref "R19")
      (value "3.9Mohm")
      (footprint "eagle-import:R0603")
      (libsource (lib "eagle-import") (part "R-EU_R0603"))
    )
    (comp (ref "R20")
      (value "3.9Mohm")
      (footprint "eagle-import:R0603")
      (libsource (lib "eagle-import") (part "R-EU_R0603"))
    )
    (comp (ref "R21")
      (value "3.9Mohm")
      (footprint "eagle-import:R0603")
      (libsource (lib "eagle-import") (part "R-EU_R0603"))
    )
    (comp (ref "R22")
      (value "3.9Mohm")
      (footprint "eagle-import:R0603")
      (libsource (lib "eagle-import") (part "R-EU_R0603"))
    )
    (comp (ref "R23")
      (value "3.9Mohm")
      (footprint "eagle-import:R0603")
      (libsource (lib "eagle-import") (part "R-EU_R0603"))
    )
    (comp (ref "R24")
      (value "3.9Mohm")
      (footprint "eagle-import:R0603")
      (libsource (lib "eagle-import") (part "R-EU_R0603"))
    )
    (comp (ref "R25")
      (value "3.9Mohm")
      (footprint "eagle-import:R0603")
      (libsource (lib "eagle-import") (part "R-EU_R0603"))
    )
    (comp (ref "R26")
      (value "3.9Mohm")
      (footprint "eagle-import:R0603")
      (libsource (lib "eagle-import") (part "R-EU_R0603"))
    )
    (comp (ref "R27")
      (value "3.9Mohm")
      (footprint "eagle-import:R0603")
      (libsource (lib "eagle-import") (part "R-EU_R0603"))
    )
    (comp (ref "R28")
      (value "3.9Mohm")
      (footprint "eagle-import:R0603")
      (libsource (lib "eagle-import") (part "R-EU_R0603"))
    )
    (comp (ref "R29")
      (value "3.9Mohm")
      (footprint "eagle-import:R0603")
      (libsource (lib "eagle-import") (part "R-EU_R0603"))
    )
    (comp (ref "R30")
      (value "3.9Mohm")
      (footprint "eagle-import:R0603")
      (libsource (lib "eagle-import") (part "R-EU_R0603"))
    )
    (comp (ref "R31")
      (value "3.9Mohm")
      (footprint "eagle-import:R0603")
      (libsource (lib "eagle-import") (part "R-EU_R0603"))
    )
    (comp (ref "R32")
      (value "3.9Mohm")
      (footprint "eagle-import:R0603")
      (libsource (lib "eagle-import") (part "R-EU_R0603"))
    )
    (comp (ref "R33")
      (value "3.9Mohm")
      (footprint "eagle-import:R0603")
      (libsource (lib "eagle-import") (part "R-EU_R0603"))
    )
    (comp (ref "R34")
      (value "3.9Mohm")
      (footprint "eagle-import:R0603")
      (libsource (lib "eagle-import") (part "R-EU_R0603"))
    )
    (comp (ref "R35")
      (value "3.9Mohm")
      (footprint "eagle-import:R0603")
      (libsource (lib "eagle-import") (part "R-EU_R0603"))
    )
    (comp (ref "R36")
      (value "3.9Mohm")
      (footprint "eagle-import:R0603")
      (libsource (lib "eagle-import") (part "R-EU_R0603"))
    )
    (comp (ref "R37")
      (value "3.9Mohm")
      (footprint "eagle-import:R0603")
      (libsource (lib "eagle-import") (part "R-EU_R0603"))
    )
    (comp (ref "R38")
      (value "3.9Mohm")
      (footprint "eagle-import:R0603")
      (libsource (lib "eagle-import") (part "R-EU_R0603"))
    )
    (comp (ref "R39")
      (value "3.9Mohm")
      (footprint "eagle-import:R0603")
      (libsource (lib "eagle-import") (part "R-EU_R0603"))
    )
    (comp (ref "R40")
      (value "3.9Mohm")
      (footprint "eagle-import:R0603")
      (libsource (lib "eagle-import") (part "R-EU_R0603"))
    )
    (comp (ref "R41")
      (value "3.9Mohm")
      (footprint "eagle-import:R0603")
      (libsource (lib "eagle-import") (part "R-EU_R0603"))
    )
    (comp (ref "R42")
      (value "3.9Mohm")
      (footprint "eagle-import:R0603")
      (libsource (lib "eagle-import") (part "R-EU_R0603"))
    )
    (comp (ref "R43")
      (value "3.9Mohm")
      (footprint "eagle-import:R0603")
      (libsource (lib "eagle-import") (part "R-EU_R0603"))
    )
    (comp (ref "R44")
      (value "3.9Mohm")
      (footprint "eagle-import:R0603")
      (libsource (lib "eagle-import") (part "R-EU_R0603"))
    )
    (comp (ref "R45")
      (value "3.9Mohm")
      (footprint "eagle-import:R0603")
      (libsource (lib "eagle-import") (part "R-EU_R0603"))
    )
    (comp (ref "R46")
      (value "3.9Mohm")
      (footprint "eagle-import:R0603")
      (libsource (lib "eagle-import") (part "R-EU_R0603"))
    )
    (comp (ref "R47")
      (value "3.9Mohm")
      (footprint "eagle-import:R0603")
      (libsource (lib "eagle-import") (part "R-EU_R0603"))
    )
    (comp (ref "R48")
      (value "3.9Mohm")
      (footprint "eagle-import:R0603")
      (libsource (lib "eagle-import") (part "R-EU_R0603"))
    )
    (comp (ref "R49")
      (value "3.9Mohm")
      (footprint "eagle-import:R0603")
      (libsource (lib "eagle-import") (part "R-EU_R0603"))
    )
    (comp (ref "R50")
      (value "3.9Mohm")
      (footprint "eagle-import:R0603")
      (libsource (lib "eagle-import") (part "R-EU_R0603"))
    )
    (comp (ref "R51")
      (value "3.9Mohm")
      (footprint "eagle-import:R0603")
      (libsource (lib "eagle-import") (part "R-EU_R0603"))
    )
    (comp (ref "R52")
      (value "3.9Mohm")
      (footprint "eagle-import:R0603")
      (libsource (lib "eagle-import") (part "R-EU_R0603"))
    )
    (comp (ref "R53")
      (value "3.9Mohm")
      (footprint "eagle-import:R0603")
      (libsource (lib "eagle-import") (part "R-EU_R0603"))
    )
    (comp (ref "R54")
      (value "3.9Mohm")
      (footprint "eagle-import:R0603")
      (libsource (lib "eagle-import") (part "R-EU_R0603"))
    )
    (comp (ref "R55")
      (value "3.9Mohm")
      (footprint "eagle-import:R0603")
      (libsource (lib "eagle-import") (part "R-EU_R0603"))
    )
    (comp (ref "R56")
      (value "3.9Mohm")
      (footprint "eagle-import:R0603")
      (libsource (lib "eagle-import") (part "R-EU_R0603"))
    )
    (comp (ref "R57")
      (value "3.9Mohm")
      (footprint "eagle-import:R0603")
      (libsource (lib "eagle-import") (part "R-EU_R0603"))
    )
    (comp (ref "R58")
      (value "3.9Mohm")
      (footprint "eagle-import:R0603")
      (libsource (lib "eagle-import") (part "R-EU_R0603"))
    )
    (comp (ref "R59")
      (value "3.9Mohm")
      (footprint "eagle-import:R0603")
      (libsource (lib "eagle-import") (part "R-EU_R0603"))
    )
    (comp (ref "R60")
      (value "3.9Mohm")
      (footprint "eagle-import:R0603")
      (libsource (lib "eagle-import") (part "R-EU_R0603"))
    )
    (comp (ref "R61")
      (value "3.9Mohm")
      (footprint "eagle-import:R0603")
      (libsource (lib "eagle-import") (part "R-EU_R0603"))
    )
    (comp (ref "R62")
      (value "3.9Mohm")
      (footprint "eagle-import:R0603")
      (libsource (lib "eagle-import") (part "R-EU_R0603"))
    )
    (comp (ref "R63")
      (value "3.9Mohm")
      (footprint "eagle-import:R0603")
      (libsource (lib "eagle-import") (part "R-EU_R0603"))
    )
    (comp (ref "R64")
      (value "3.9Mohm")
      (footprint "eagle-import:R0603")
      (libsource (lib "eagle-import") (part "R-EU_R0603"))
    )
    (comp (ref "R65")
      (value "3.9Mohm")
      (footprint "eagle-import:R0603")
      (libsource (lib "eagle-import") (part "R-EU_R0603"))
    )
    (comp (ref "R66")
      (value "3.9Mohm")
      (footprint "eagle-import:R0603")
      (libsource (lib "eagle-import") (part "R-EU_R0603"))
    )
    (comp (ref "R67")
      (value "3.9Mohm")
      (footprint "eagle-import:R0603")
      (libsource (lib "eagle-import") (part "R-EU_R0603"))
    )
    (comp (ref "R68")
      (value "3.9Mohm")
      (footprint "eagle-import:R0603")
      (libsource (lib "eagle-import") (part "R-EU_R0603"))
    )
    (comp (ref "R69")
      (value "3.9Mohm")
      (footprint "eagle-import:R0603")
      (libsource (lib "eagle-import") (part "R-EU_R0603"))
    )
    (comp (ref "R70")
      (value "3.9Mohm")
      (footprint "eagle-import:R0603")
      (libsource (lib "eagle-import") (part "R-EU_R0603"))
    )
    (comp (ref "R71")
      (value "3.9Mohm")
      (footprint "eagle-import:R0603")
      (libsource (lib "eagle-import") (part "R-EU_R0603"))
    )
    (comp (ref "R72")
      (value "3.9Mohm")
      (footprint "eagle-import:R0603")
      (libsource (lib "eagle-import") (part "R-EU_R0603"))
    )
    (comp (ref "R73")
      (value "3.9Mohm")
      (footprint "eagle-import:R0603")
      (libsource (lib "eagle-import") (part "R-EU_R0603"))
    )
    (comp (ref "R74")
      (value "3.9Mohm")
      (footprint "eagle-import:R0603")
      (libsource (lib "eagle-import") (part "R-EU_R0603"))
    )
    (comp (ref "R75")
      (value "3.9Mohm")
      (footprint "eagle-import:R0603")
      (libsource (lib "eagle-import") (part "R-EU_R0603"))
    )
    (comp (ref "R76")
      (value "3.9Mohm")
      (footprint "eagle-import:R0603")
      (libsource (lib "eagle-import") (part "R-EU_R0603"))
    )
    (comp (ref "R77")
      (value "3.9Mohm")
      (footprint "eagle-import:R0603")
      (libsource (lib "eagle-import") (part "R-EU_R0603"))
    )
    (comp (ref "R78")
      (value "3.9Mohm")
      (footprint "eagle-import:R0603")
      (libsource (lib "eagle-import") (part "R-EU_R0603"))
    )
    (comp (ref "R79")
      (value "3.9Mohm")
      (footprint "eagle-import:R0603")
      (libsource (lib "eagle-import") (part "R-EU_R0603"))
    )
    (comp (ref "R80")
      (value "3.9Mohm")
      (footprint "eagle-import:R0603")
      (libsource (lib "eagle-import") (part "R-EU_R0603"))
    )
    (comp (ref "R81")
      (value "3.9Mohm")
      (footprint "eagle-import:R0603")
      (libsource (lib "eagle-import") (part "R-EU_R0603"))
    )
    (comp (ref "R82")
      (value "3.9Mohm")
      (footprint "eagle-import:R0603")
      (libsource (lib "eagle-import") (part "R-EU_R0603"))
    )
    (comp (ref "R83")
      (value "3.9Mohm")
      (footprint "eagle-import:R0603")
      (libsource (lib "eagle-import") (part "R-EU_R0603"))
    )
    (comp (ref "R84")
      (value "3.9Mohm")
      (footprint "eagle-import:R0603")
      (libsource (lib "eagle-import") (part "R-EU_R0603"))
    )
    (comp (ref "R85")
      (value "3.9Mohm")
      (footprint "eagle-import:R0603")
      (libsource (lib "eagle-import") (part "R-EU_R0603"))
    )
    (comp (ref "R86")
      (value "3.9Mohm")
      (footprint "eagle-import:R0603")
      (libsource (lib "eagle-import") (part "R-EU_R0603"))
    )
    (comp (ref "R87")
      (value "3.9Mohm")
      (footprint "eagle-import:R0603")
      (libsource (lib "eagle-import") (part "R-EU_R0603"))
    )
    (comp (ref "R88")
      (value "3.9Mohm")
      (footprint "eagle-import:R0603")
      (libsource (lib "eagle-import") (part "R-EU_R0603"))
    )
    (comp (ref "R89")
      (value "3.9Mohm")
      (footprint "eagle-import:R0603")
      (libsource (lib "eagle-import") (part "R-EU_R0603"))
    )
    (comp (ref "R90")
      (value "3.9Mohm")
      (footprint "eagle-import:R0603")
      (libsource (lib "eagle-import") (part "R-EU_R0603"))
    )
    (comp (ref "R91")
      (value "3.9Mohm")
      (footprint "eagle-import:R0603")
      (libsource (lib "eagle-import") (part "R-EU_R0603"))
    )
    (comp (ref "R92")
      (value "3.9Mohm")
      (footprint "eagle-import:R0603")
      (libsource (lib "eagle-import") (part "R-EU_R0603"))
    )
    (comp (ref "R93")
      (value "3.9Mohm")
      (footprint "eagle-import:R0603")
      (libsource (lib "eagle-import") (part "R-EU_R0603"))
    )
    (comp (ref "R94")
      (value "3.9Mohm")
      (footprint "eagle-import:R0603")
      (libsource (lib "eagle-import") (part "R-EU_R0603"))
    )
    (comp (ref "R95")
      (value "3.9Mohm")
      (footprint "eagle-import:R0603")
      (libsource (lib "eagle-import") (part "R-EU_R0603"))
    )
    (comp (ref "R96")
      (value "3.9Mohm")
      (footprint "eagle-import:R0603")
      (libsource (lib "eagle-import") (part "R-EU_R0603"))
    )
    (comp (ref "R97")
      (value "3.9Mohm")
      (footprint "eagle-import:R0603")
      (libsource (lib "eagle-import") (part "R-EU_R0603"))
    )
    (comp (ref "U1")
      (value "74HC4067")
      (footprint "eagle-import:SSOP24")
      (libsource (lib "eagle-import") (part "MUX-1X16"))
    )
    (comp (ref "U2")
      (value "74HC4067")
      (footprint "eagle-import:SSOP24")
      (libsource (lib "eagle-import") (part "MUX-1X16"))
    )
    (comp (ref "U3")
      (value "74HC4067")
      (footprint "eagle-import:SSOP24")
      (libsource (lib "eagle-import") (part "MUX-1X16"))
    )
    (comp (ref "U4")
      (value "74HC4067")
      (footprint "eagle-import:SSOP24")
      (libsource (lib "eagle-import") (part "MUX-1X16"))
    )
    (comp (ref "U5")
      (value "74HC4067")
      (footprint "eagle-import:SSOP24")
      (libsource (lib "eagle-import") (part "MUX-1X16"))
    )
    (comp (ref "U6")
      (value "74HC4067")
      (footprint "eagle-import:SSOP24")
      (libsource (lib "eagle-import") (part "MUX-1X16"))
    )
    (comp (ref "X1")
      (value "MKDSN1,5/2-5,08")
      (footprint "eagle-import:MKDSN1,5_2-5,08")
      (libsource (lib "eagle-import") (part "MKDSN1,5/2-5,08"))
    )
    (comp (ref "X2")
      (value "MKDSN1,5/10-5,08")
      (footprint "eagle-import:MKDSN1,5_10-5,08")
      (libsource (lib "eagle-import") (part "MKDSN1,5/10-5,08"))
    )
  )
  (nets
    (net (code "1") (name "+5V") (class "Default")
      (node (ref "C1") (pin "1") (pinfunction "1_1") (pintype "passive"))
      (node (ref "C10") (pin "1") (pinfunction "1_1") (pintype "passive"))
      (node (ref "C11") (pin "1") (pinfunction "1_1") (pintype "passive"))
      (node (ref "C12") (pin "1") (pinfunction "1_1") (pintype "passive"))
      (node (ref "C13") (pin "1") (pinfunction "1_1") (pintype "passive"))
      (node (ref "C14") (pin "1") (pinfunction "1_1") (pintype "passive"))
      (node (ref "C15") (pin "1") (pinfunction "1_1") (pintype "passive"))
      (node (ref "C16") (pin "1") (pinfunction "1_1") (pintype "passive"))
      (node (ref "C17") (pin "1") (pinfunction "1_1") (pintype "passive"))
      (node (ref "C18") (pin "1") (pinfunction "1_1") (pintype "passive"))
      (node (ref "C19") (pin "1") (pinfunction "1_1") (pintype "passive"))
      (node (ref "C2") (pin "1") (pinfunction "1_1") (pintype "passive"))
      (node (ref "C20") (pin "1") (pinfunction "1_1") (pintype "passive"))
      (node (ref "C21") (pin "1") (pinfunction "1_1") (pintype "passive"))
      (node (ref "C22") (pin "1") (pinfunction "1_1") (pintype "passive"))
      (node (ref "C23") (pin "1") (pinfunction "1_1") (pintype "passive"))
      (node (ref "C25") (pin "1") (pinfunction "1_1") (pintype "passive"))
      (node (ref "C3") (pin "1") (pinfunction "1_1") (pintype "passive"))
      (node (ref "C4") (pin "1") (pinfunction "1_1") (pintype "passive"))
      (node (ref "C5") (pin "1") (pinfunction "1_1") (pintype "passive"))
      (node (ref "C6") (pin "1") (pinfunction "1_1") (pintype "passive"))
      (node (ref "C7") (pin "1") (pinfunction "1_1") (pintype "passive"))
      (node (ref "C8") (pin "1") (pinfunction "1_1") (pintype "passive"))
      (node (ref "C9") (pin "1") (pinfunction "1_1") (pintype "passive"))
      (node (ref "IC1") (pin "4") (pinfunction "V+_4") (pintype "power_in"))
      (node (ref "IC10") (pin "4") (pinfunction "V+_4") (pintype "power_in"))
      (node (ref "IC11") (pin "4") (pinfunction "V+_4") (pintype "power_in"))
      (node (ref "IC12") (pin "4") (pinfunction "V+_4") (pintype "power_in"))
      (node (ref "IC13") (pin "4") (pinfunction "V+_4") (pintype "power_in"))
      (node (ref "IC14") (pin "4") (pinfunction "V+_4") (pintype "power_in"))
      (node (ref "IC15") (pin "4") (pinfunction "V+_4") (pintype "power_in"))
      (node (ref "IC16") (pin "4") (pinfunction "V+_4") (pintype "power_in"))
      (node (ref "IC17") (pin "4") (pinfunction "V+_4") (pintype "power_in"))
      (node (ref "IC18") (pin "4") (pinfunction "V+_4") (pintype "power_in"))
      (node (ref "IC19") (pin "4") (pinfunction "V+_4") (pintype "power_in"))
      (node (ref "IC2") (pin "4") (pinfunction "V+_4") (pintype "power_in"))
      (node (ref "IC20") (pin "4") (pinfunction "V+_4") (pintype "power_in"))
      (node (ref "IC21") (pin "4") (pinfunction "V+_4") (pintype "power_in"))
      (node (ref "IC22") (pin "4") (pinfunction "V+_4") (pintype "power_in"))
      (node (ref "IC23") (pin "4") (pinfunction "V+_4") (pintype "power_in"))
      (node (ref "IC24") (pin "4") (pinfunction "V+_4") (pintype "power_in"))
      (node (ref "IC3") (pin "4") (pinfunction "V+_4") (pintype "power_in"))
      (node (ref "IC4") (pin "4") (pinfunction "V+_4") (pintype "power_in"))
      (node (ref "IC5") (pin "4") (pinfunction "V+_4") (pintype "power_in"))
      (node (ref "IC6") (pin "4") (pinfunction "V+_4") (pintype "power_in"))
      (node (ref "IC7") (pin "4") (pinfunction "V+_4") (pintype "power_in"))
      (node (ref "IC8") (pin "4") (pinfunction "V+_4") (pintype "power_in"))
      (node (ref "IC9") (pin "4") (pinfunction "V+_4") (pintype "power_in"))
      (node (ref "U1") (pin "24") (pinfunction "VCC_24") (pintype "bidirectional"))
      (node (ref "U2") (pin "24") (pinfunction "VCC_24") (pintype "bidirectional"))
      (node (ref "U3") (pin "24") (pinfunction "VCC_24") (pintype "bidirectional"))
      (node (ref "U4") (pin "24") (pinfunction "VCC_24") (pintype "bidirectional"))
      (node (ref "U5") (pin "24") (pinfunction "VCC_24") (pintype "bidirectional"))
      (node (ref "U6") (pin "24") (pinfunction "VCC_24") (pintype "bidirectional"))
      (node (ref "X1") (pin "2") (pinfunction "KL_2") (pintype "passive"))
    )
    (net (code "2") (name "/AO1") (class "Default")
      (node (ref "IC10") (pin "1") (pinfunction "OUT_1") (pintype "output"))
      (node (ref "R11") (pin "2") (pinfunction "2_2") (pintype "passive"))
      (node (ref "U1") (pin "2") (pinfunction "CH7_2") (pintype "bidirectional"))
    )
    (net (code "3") (name "/AO2") (class "Default")
      (node (ref "IC10") (pin "7") (pinfunction "OUT_7") (pintype "output"))
      (node (ref "R22") (pin "2") (pinfunction "2_2") (pintype "passive"))
      (node (ref "U1") (pin "3") (pinfunction "CH6_3") (pintype "bidirectional"))
    )
    (net (code "4") (name "/AO3") (class "Default")
      (node (ref "IC11") (pin "1") (pinfunction "OUT_1") (pintype "output"))
      (node (ref "R12") (pin "2") (pinfunction "2_2") (pintype "passive"))
      (node (ref "U1") (pin "4") (pinfunction "CH5_4") (pintype "bidirectional"))
    )
    (net (code "5") (name "/AO4") (class "Default")
      (node (ref "IC11") (pin "7") (pinfunction "OUT_7") (pintype "output"))
      (node (ref "R23") (pin "2") (pinfunction "2_2") (pintype "passive"))
      (node (ref "U1") (pin "5") (pinfunction "CH4_5") (pintype "bidirectional"))
    )
    (net (code "6") (name "/AO5") (class "Default")
      (node (ref "IC8") (pin "1") (pinfunction "OUT_1") (pintype "output"))
      (node (ref "R9") (pin "2") (pinfunction "2_2") (pintype "passive"))
      (node (ref "U1") (pin "23") (pinfunction "CH8_23") (pintype "bidirectional"))
    )
    (net (code "7") (name "/AO6") (class "Default")
      (node (ref "IC8") (pin "7") (pinfunction "OUT_7") (pintype "output"))
      (node (ref "R20") (pin "2") (pinfunction "2_2") (pintype "passive"))
      (node (ref "U1") (pin "22") (pinfunction "CH9_22") (pintype "bidirectional"))
    )
    (net (code "8") (name "/AO7") (class "Default")
      (node (ref "IC7") (pin "1") (pinfunction "OUT_1") (pintype "output"))
      (node (ref "R8") (pin "2") (pinfunction "2_2") (pintype "passive"))
      (node (ref "U1") (pin "21") (pinfunction "CH10_21") (pintype "bidirectional"))
    )
    (net (code "9") (name "/AO8") (class "Default")
      (node (ref "IC7") (pin "7") (pinfunction "OUT_7") (pintype "output"))
      (node (ref "R19") (pin "2") (pinfunction "2_2") (pintype "passive"))
      (node (ref "U1") (pin "20") (pinfunction "CH11_20") (pintype "bidirectional"))
    )
    (net (code "10") (name "/AO9") (class "Default")
      (node (ref "IC10") (pin "14") (pinfunction "OUT_14") (pintype "output"))
      (node (ref "R38") (pin "2") (pinfunction "2_2") (pintype "passive"))
      (node (ref "U1") (pin "6") (pinfunction "CH3_6") (pintype "bidirectional"))
    )
    (net (code "11") (name "/AO10") (class "Default")
      (node (ref "IC10") (pin "8") (pinfunction "OUT_8") (pintype "output"))
      (node (ref "R30") (pin "2") (pinfunction "2_2") (pintype "passive"))
      (node (ref "U1") (pin "7") (pinfunction "CH2_7") (pintype "bidirectional"))
    )
    (net (code "12") (name "/AO11") (class "Default")
      (node (ref "IC11") (pin "14") (pinfunction "OUT_14") (pintype "output"))
      (node (ref "R39") (pin "2") (pinfunction "2_2") (pintype "passive"))
      (node (ref "U1") (pin "8") (pinfunction "CH1_8") (pintype "bidirectional"))
    )
    (net (code "13") (name "/AO12") (class "Default")
      (node (ref "IC11") (pin "8") (pinfunction "OUT_8") (pintype "output"))
      (node (ref "R31") (pin "2") (pinfunction "2_2") (pintype "passive"))
      (node (ref "U1") (pin "9") (pinfunction "CH0_9") (pintype "bidirectional"))
    )
    (net (code "14") (name "/AO13") (class "Default")
      (node (ref "IC8") (pin "14") (pinfunction "OUT_14") (pintype "output"))
      (node (ref "R36") (pin "2") (pinfunction "2_2") (pintype "passive"))
      (node (ref "U1") (pin "19") (pinfunction "CH12_19") (pintype "bidirectional"))
    )
    (net (code "15") (name "/AO14") (class "Default")
      (node (ref "IC8") (pin "8") (pinfunction "OUT_8") (pintype "output"))
      (node (ref "R27") (pin "2") (pinfunction "2_2") (pintype "passive"))
      (node (ref "U1") (pin "18") (pinfunction "CH13_18") (pintype "bidirectional"))
    )
    (net (code "16") (name "/AO15") (class "Default")
      (node (ref "IC7") (pin "14") (pinfunction "OUT_14") (pintype "output"))
      (node (ref "R35") (pin "2") (pinfunction "2_2") (pintype "passive"))
      (node (ref "U1") (pin "17") (pinfunction "CH14_17") (pintype "bidirectional"))
    )
    (net (code "17") (name "/AO16") (class "Default")
      (node (ref "IC7") (pin "8") (pinfunction "OUT_8") (pintype "output"))
      (node (ref "R26") (pin "2") (pinfunction "2_2") (pintype "passive"))
      (node (ref "U1") (pin "16") (pinfunction "CH15_16") (pintype "bidirectional"))
    )
    (net (code "18") (name "/AR0") (class "Default")
      (node (ref "U1") (pin "1") (pinfunction "COM_1") (pintype "bidirectional"))
      (node (ref "X2") (pin "10") (pinfunction "KL_10") (pintype "passive"))
    )
    (net (code "19") (name "/AR1") (class "Default")
      (node (ref "U3") (pin "1") (pinfunction "COM_1") (pintype "bidirectional"))
      (node (ref "X2") (pin "9") (pinfunction "KL_9") (pintype "passive"))
    )
    (net (code "20") (name "/AR2") (class "Default")
      (node (ref "U5") (pin "1") (pinfunction "COM_1") (pintype "bidirectional"))
      (node (ref "X2") (pin "8") (pinfunction "KL_8") (pintype "passive"))
    )
    (net (code "21") (name "/AR3") (class "Default")
      (node (ref "U2") (pin "1") (pinfunction "COM_1") (pintype "bidirectional"))
      (node (ref "X2") (pin "7") (pinfunction "KL_7") (pintype "passive"))
    )
    (net (code "22") (name "/AR4") (class "Default")
      (node (ref "U4") (pin "1") (pinfunction "COM_1") (pintype "bidirectional"))
      (node (ref "X2") (pin "6") (pinfunction "KL_6") (pintype "passive"))
    )
    (net (code "23") (name "/AR5") (class "Default")
      (node (ref "U6") (pin "1") (pinfunction "COM_1") (pintype "bidirectional"))
      (node (ref "X2") (pin "5") (pinfunction "KL_5") (pintype "passive"))
    )
    (net (code "24") (name "/BO1") (class "Default")
      (node (ref "IC17") (pin "1") (pinfunction "OUT_1") (pintype "output"))
      (node (ref "R66") (pin "2") (pinfunction "2_2") (pintype "passive"))
      (node (ref "U3") (pin "2") (pinfunction "CH7_2") (pintype "bidirectional"))
    )
    (net (code "25") (name "/BO2") (class "Default")
      (node (ref "IC17") (pin "7") (pinfunction "OUT_7") (pintype "output"))
      (node (ref "R77") (pin "2") (pinfunction "2_2") (pintype "passive"))
      (node (ref "U3") (pin "3") (pinfunction "CH6_3") (pintype "bidirectional"))
    )
    (net (code "26") (name "/BO3") (class "Default")
      (node (ref "IC20") (pin "1") (pinfunction "OUT_1") (pintype "output"))
      (node (ref "R70") (pin "2") (pinfunction "2_2") (pintype "passive"))
      (node (ref "U3") (pin "4") (pinfunction "CH5_4") (pintype "bidirectional"))
    )
    (net (code "27") (name "/BO4") (class "Default")
      (node (ref "IC20") (pin "7") (pinfunction "OUT_7") (pintype "output"))
      (node (ref "R80") (pin "2") (pinfunction "2_2") (pintype "passive"))
      (node (ref "U3") (pin "5") (pinfunction "CH4_5") (pintype "bidirectional"))
    )
    (net (code "28") (name "/BO5") (class "Default")
      (node (ref "IC2") (pin "1") (pinfunction "OUT_1") (pintype "output"))
      (node (ref "R5") (pin "2") (pinfunction "2_2") (pintype "passive"))
      (node (ref "U3") (pin "23") (pinfunction "CH8_23") (pintype "bidirectional"))
    )
    (net (code "29") (name "/BO6") (class "Default")
      (node (ref "IC2") (pin "7") (pinfunction "OUT_7") (pintype "output"))
      (node (ref "R18") (pin "2") (pinfunction "2_2") (pintype "passive"))
      (node (ref "U3") (pin "22") (pinfunction "CH9_22") (pintype "bidirectional"))
    )
    (net (code "30") (name "/BO7") (class "Default")
      (node (ref "IC1") (pin "1") (pinfunction "OUT_1") (pintype "output"))
      (node (ref "R4") (pin "2") (pinfunction "2_2") (pintype "passive"))
      (node (ref "U3") (pin "21") (pinfunction "CH10_21") (pintype "bidirectional"))
    )
    (net (code "31") (name "/BO8") (class "Default")
      (node (ref "IC1") (pin "7") (pinfunction "OUT_7") (pintype "output"))
      (node (ref "R15") (pin "2") (pinfunction "2_2") (pintype "passive"))
      (node (ref "U3") (pin "20") (pinfunction "CH11_20") (pintype "bidirectional"))
    )
    (net (code "32") (name "/BO9") (class "Default")
      (node (ref "IC17") (pin "14") (pinfunction "OUT_14") (pintype "output"))
      (node (ref "R90") (pin "2") (pinfunction "2_2") (pintype "passive"))
      (node (ref "U3") (pin "6") (pinfunction "CH3_6") (pintype "bidirectional"))
    )
    (net (code "33") (name "/BO10") (class "Default")
      (node (ref "IC17") (pin "8") (pinfunction "OUT_8") (pintype "output"))
      (node (ref "R83") (pin "2") (pinfunction "2_2") (pintype "passive"))
      (node (ref "U3") (pin "7") (pinfunction "CH2_7") (pintype "bidirectional"))
    )
    (net (code "34") (name "/BO11") (class "Default")
      (node (ref "IC20") (pin "14") (pinfunction "OUT_14") (pintype "output"))
      (node (ref "R96") (pin "2") (pinfunction "2_2") (pintype "passive"))
      (node (ref "U3") (pin "8") (pinfunction "CH1_8") (pintype "bidirectional"))
    )
    (net (code "35") (name "/BO12") (class "Default")
      (node (ref "IC20") (pin "8") (pinfunction "OUT_8") (pintype "output"))
      (node (ref "R87") (pin "2") (pinfunction "2_2") (pintype "passive"))
      (node (ref "U3") (pin "9") (pinfunction "CH0_9") (pintype "bidirectional"))
    )
    (net (code "36") (name "/BO13") (class "Default")
      (node (ref "IC2") (pin "14") (pinfunction "OUT_14") (pintype "output"))
      (node (ref "R41") (pin "2") (pinfunction "2_2") (pintype "passive"))
      (node (ref "U3") (pin "19") (pinfunction "CH12_19") (pintype "bidirectional"))
    )
    (net (code "37") (name "/BO14") (class "Default")
      (node (ref "IC2") (pin "8") (pinfunction "OUT_8") (pintype "output"))
      (node (ref "R24") (pin "2") (pinfunction "2_2") (pintype "passive"))
      (node (ref "U3") (pin "18") (pinfunction "CH13_18") (pintype "bidirectional"))
    )
    (net (code "38") (name "/BO15") (class "Default")
      (node (ref "IC1") (pin "14") (pinfunction "OUT_14") (pintype "output"))
      (node (ref "R44") (pin "2") (pinfunction "2_2") (pintype "passive"))
      (node (ref "U3") (pin "17") (pinfunction "CH14_17") (pintype "bidirectional"))
    )
    (net (code "39") (name "/BO16") (class "Default")
      (node (ref "IC1") (pin "8") (pinfunction "OUT_8") (pintype "output"))
      (node (ref "R25") (pin "2") (pinfunction "2_2") (pintype "passive"))
      (node (ref "U3") (pin "16") (pinfunction "CH15_16") (pintype "bidirectional"))
    )
    (net (code "40") (name "/CO1") (class "Default")
      (node (ref "IC13") (pin "1") (pinfunction "OUT_1") (pintype "output"))
      (node (ref "R49") (pin "2") (pinfunction "2_2") (pintype "passive"))
      (node (ref "U5") (pin "2") (pinfunction "CH7_2") (pintype "bidirectional"))
    )
    (net (code "41") (name "/CO2") (class "Default")
      (node (ref "IC13") (pin "7") (pinfunction "OUT_7") (pintype "output"))
      (node (ref "R55") (pin "2") (pinfunction "2_2") (pintype "passive"))
      (node (ref "U5") (pin "3") (pinfunction "CH6_3") (pintype "bidirectional"))
    )
    (net (code "42") (name "/CO3") (class "Default")
      (node (ref "IC12") (pin "1") (pinfunction "OUT_1") (pintype "output"))
      (node (ref "R48") (pin "2") (pinfunction "2_2") (pintype "passive"))
      (node (ref "U5") (pin "4") (pinfunction "CH5_4") (pintype "bidirectional"))
    )
    (net (code "43") (name "/CO4") (class "Default")
      (node (ref "IC12") (pin "7") (pinfunction "OUT_7") (pintype "output"))
      (node (ref "R54") (pin "2") (pinfunction "2_2") (pintype "passive"))
      (node (ref "U5") (pin "5") (pinfunction "CH4_5") (pintype "bidirectional"))
    )
    (net (code "44") (name "/CO5") (class "Default")
      (node (ref "IC23") (pin "1") (pinfunction "OUT_1") (pintype "output"))
      (node (ref "R72") (pin "2") (pinfunction "2_2") (pintype "passive"))
      (node (ref "U5") (pin "23") (pinfunction "CH8_23") (pintype "bidirectional"))
    )
    (net (code "45") (name "/CO6") (class "Default")
      (node (ref "IC23") (pin "7") (pinfunction "OUT_7") (pintype "output"))
      (node (ref "R76") (pin "2") (pinfunction "2_2") (pintype "passive"))
      (node (ref "U5") (pin "22") (pinfunction "CH9_22") (pintype "bidirectional"))
    )
    (net (code "46") (name "/CO7") (class "Default")
      (node (ref "IC19") (pin "1") (pinfunction "OUT_1") (pintype "output"))
      (node (ref "R71") (pin "2") (pinfunction "2_2") (pintype "passive"))
      (node (ref "U5") (pin "21") (pinfunction "CH10_21") (pintype "bidirectional"))
    )
    (net (code "47") (name "/CO8") (class "Default")
      (node (ref "IC19") (pin "7") (pinfunction "OUT_7") (pintype "output"))
      (node (ref "R75") (pin "2") (pinfunction "2_2") (pintype "passive"))
      (node (ref "U5") (pin "20") (pinfunction "CH11_20") (pintype "bidirectional"))
    )
    (net (code "48") (name "/CO9") (class "Default")
      (node (ref "IC13") (pin "14") (pinfunction "OUT_14") (pintype "output"))
      (node (ref "R65") (pin "2") (pinfunction "2_2") (pintype "passive"))
      (node (ref "U5") (pin "6") (pinfunction "CH3_6") (pintype "bidirectional"))
    )
    (net (code "49") (name "/CO10") (class "Default")
      (node (ref "IC13") (pin "8") (pinfunction "OUT_8") (pintype "output"))
      (node (ref "R60") (pin "2") (pinfunction "2_2") (pintype "passive"))
      (node (ref "U5") (pin "7") (pinfunction "CH2_7") (pintype "bidirectional"))
    )
    (net (code "50") (name "/CO11") (class "Default")
      (node (ref "IC12") (pin "14") (pinfunction "OUT_14") (pintype "output"))
      (node (ref "R64") (pin "2") (pinfunction "2_2") (pintype "passive"))
      (node (ref "U5") (pin "8") (pinfunction "CH1_8") (pintype "bidirectional"))
    )
    (net (code "51") (name "/CO12") (class "Default")
      (node (ref "IC12") (pin "8") (pinfunction "OUT_8") (pintype "output"))
      (node (ref "R59") (pin "2") (pinfunction "2_2") (pintype "passive"))
      (node (ref "U5") (pin "9") (pinfunction "CH0_9") (pintype "bidirectional"))
    )
    (net (code "52") (name "/CO13") (class "Default")
      (node (ref "IC23") (pin "14") (pinfunction "OUT_14") (pintype "output"))
      (node (ref "R94") (pin "2") (pinfunction "2_2") (pintype "passive"))
      (node (ref "U5") (pin "19") (pinfunction "CH12_19") (pintype "bidirectional"))
    )
    (net (code "53") (name "/CO14") (class "Default")
      (node (ref "IC23") (pin "8") (pinfunction "OUT_8") (pintype "output"))
      (node (ref "R82") (pin "2") (pinfunction "2_2") (pintype "passive"))
      (node (ref "U5") (pin "18") (pinfunction "CH13_18") (pintype "bidirectional"))
    )
    (net (code "54") (name "/CO15") (class "Default")
      (node (ref "IC19") (pin "14") (pinfunction "OUT_14") (pintype "output"))
      (node (ref "R92") (pin "2") (pinfunction "2_2") (pintype "passive"))
      (node (ref "U5") (pin "17") (pinfunction "CH14_17") (pintype "bidirectional"))
    )
    (net (code "55") (name "/CO16") (class "Default")
      (node (ref "IC19") (pin "8") (pinfunction "OUT_8") (pintype "output"))
      (node (ref "R86") (pin "2") (pinfunction "2_2") (pintype "passive"))
      (node (ref "U5") (pin "16") (pinfunction "CH15_16") (pintype "bidirectional"))
    )
    (net (code "56") (name "/DO1") (class "Default")
      (node (ref "IC6") (pin "1") (pinfunction "OUT_1") (pintype "output"))
      (node (ref "R1") (pin "2") (pinfunction "2_2") (pintype "passive"))
      (node (ref "U2") (pin "2") (pinfunction "CH7_2") (pintype "bidirectional"))
    )
    (net (code "57") (name "/DO2") (class "Default")
      (node (ref "IC6") (pin "7") (pinfunction "OUT_7") (pintype "output"))
      (node (ref "R14") (pin "2") (pinfunction "2_2") (pintype "passive"))
      (node (ref "U2") (pin "3") (pinfunction "CH6_3") (pintype "bidirectional"))
    )
    (net (code "58") (name "/DO3") (class "Default")
      (node (ref "IC16") (pin "1") (pinfunction "OUT_1") (pintype "output"))
      (node (ref "R47") (pin "2") (pinfunction "2_2") (pintype "passive"))
      (node (ref "U2") (pin "4") (pinfunction "CH5_4") (pintype "bidirectional"))
    )
    (net (code "59") (name "/DO4") (class "Default")
      (node (ref "IC16") (pin "7") (pinfunction "OUT_7") (pintype "output"))
      (node (ref "R51") (pin "2") (pinfunction "2_2") (pintype "passive"))
      (node (ref "U2") (pin "5") (pinfunction "CH4_5") (pintype "bidirectional"))
    )
    (net (code "60") (name "/DO5") (class "Default")
      (node (ref "IC18") (pin "1") (pinfunction "OUT_1") (pintype "output"))
      (node (ref "R69") (pin "2") (pinfunction "2_2") (pintype "passive"))
      (node (ref "U2") (pin "23") (pinfunction "CH8_23") (pintype "bidirectional"))
    )
    (net (code "61") (name "/DO6") (class "Default")
      (node (ref "IC18") (pin "7") (pinfunction "OUT_7") (pintype "output"))
      (node (ref "R74") (pin "2") (pinfunction "2_2") (pintype "passive"))
      (node (ref "U2") (pin "22") (pinfunction "CH9_22") (pintype "bidirectional"))
    )
    (net (code "62") (name "/DO7") (class "Default")
      (node (ref "IC4") (pin "1") (pinfunction "OUT_1") (pintype "output"))
      (node (ref "R3") (pin "2") (pinfunction "2_2") (pintype "passive"))
      (node (ref "U2") (pin "21") (pinfunction "CH10_21") (pintype "bidirectional"))
    )
    (net (code "63") (name "/DO8") (class "Default")
      (node (ref "IC4") (pin "7") (pinfunction "OUT_7") (pintype "output"))
      (node (ref "R16") (pin "2") (pinfunction "2_2") (pintype "passive"))
      (node (ref "U2") (pin "20") (pinfunction "CH11_20") (pintype "bidirectional"))
    )
    (net (code "64") (name "/DO9") (class "Default")
      (node (ref "IC6") (pin "14") (pinfunction "OUT_14") (pintype "output"))
      (node (ref "R42") (pin "2") (pinfunction "2_2") (pintype "passive"))
      (node (ref "U2") (pin "6") (pinfunction "CH3_6") (pintype "bidirectional"))
    )
    (net (code "65") (name "/DO10") (class "Default")
      (node (ref "IC6") (pin "8") (pinfunction "OUT_8") (pintype "output"))
      (node (ref "R29") (pin "2") (pinfunction "2_2") (pintype "passive"))
      (node (ref "U2") (pin "7") (pinfunction "CH2_7") (pintype "bidirectional"))
    )
    (net (code "66") (name "/DO11") (class "Default")
      (node (ref "IC16") (pin "14") (pinfunction "OUT_14") (pintype "output"))
      (node (ref "R61") (pin "2") (pinfunction "2_2") (pintype "passive"))
      (node (ref "U2") (pin "8") (pinfunction "CH1_8") (pintype "bidirectional"))
    )
    (net (code "67") (name "/DO12") (class "Default")
      (node (ref "IC16") (pin "8") (pinfunction "OUT_8") (pintype "output"))
      (node (ref "R57") (pin "2") (pinfunction "2_2") (pintype "passive"))
      (node (ref "U2") (pin "9") (pinfunction "CH0_9") (pintype "bidirectional"))
    )
    (net (code "68") (name "/DO13") (class "Default")
      (node (ref "IC18") (pin "14") (pinfunction "OUT_14") (pintype "output"))
      (node (ref "R91") (pin "2") (pinfunction "2_2") (pintype "passive"))
      (node (ref "U2") (pin "19") (pinfunction "CH12_19") (pintype "bidirectional"))
    )
    (net (code "69") (name "/DO14") (class "Default")
      (node (ref "IC18") (pin "8") (pinfunction "OUT_8") (pintype "output"))
      (node (ref "R85") (pin "2") (pinfunction "2_2") (pintype "passive"))
      (node (ref "U2") (pin "18") (pinfunction "CH13_18") (pintype "bidirectional"))
    )
    (net (code "70") (name "/DO15") (class "Default")
      (node (ref "IC4") (pin "14") (pinfunction "OUT_14") (pintype "output"))
      (node (ref "R40") (pin "2") (pinfunction "2_2") (pintype "passive"))
      (node (ref "U2") (pin "17") (pinfunction "CH14_17") (pintype "bidirectional"))
    )
    (net (code "71") (name "/DO16") (class "Default")
      (node (ref "IC4") (pin "8") (pinfunction "OUT_8") (pintype "output"))
      (node (ref "R32") (pin "2") (pinfunction "2_2") (pintype "passive"))
      (node (ref "U2") (pin "16") (pinfunction "CH15_16") (pintype "bidirectional"))
    )
    (net (code "72") (name "/EO1") (class "Default")
      (node (ref "IC14") (pin "1") (pinfunction "OUT_1") (pintype "output"))
      (node (ref "R46") (pin "2") (pinfunction "2_2") (pintype "passive"))
      (node (ref "U4") (pin "2") (pinfunction "CH7_2") (pintype "bidirectional"))
    )
    (net (code "73") (name "/EO2") (class "Default")
      (node (ref "IC14") (pin "7") (pinfunction "OUT_7") (pintype "output"))
      (node (ref "R52") (pin "2") (pinfunction "2_2") (pintype "passive"))
      (node (ref "U4") (pin "3") (pinfunction "CH6_3") (pintype "bidirectional"))
    )
    (net (code "74") (name "/EO3") (class "Default")
      (node (ref "IC24") (pin "1") (pinfunction "OUT_1") (pintype "output"))
      (node (ref "R67") (pin "2") (pinfunction "2_2") (pintype "passive"))
      (node (ref "U4") (pin "4") (pinfunction "CH5_4") (pintype "bidirectional"))
    )
    (net (code "75") (name "/EO4") (class "Default")
      (node (ref "IC24") (pin "7") (pinfunction "OUT_7") (pintype "output"))
      (node (ref "R78") (pin "2") (pinfunction "2_2") (pintype "passive"))
      (node (ref "U4") (pin "5") (pinfunction "CH4_5") (pintype "bidirectional"))
    )
    (net (code "76") (name "/EO5") (class "Default")
      (node (ref "IC5") (pin "1") (pinfunction "OUT_1") (pintype "output"))
      (node (ref "R7") (pin "2") (pinfunction "2_2") (pintype "passive"))
      (node (ref "U4") (pin "23") (pinfunction "CH8_23") (pintype "bidirectional"))
    )
    (net (code "77") (name "/EO6") (class "Default")
      (node (ref "IC5") (pin "7") (pinfunction "OUT_7") (pintype "output"))
      (node (ref "R13") (pin "2") (pinfunction "2_2") (pintype "passive"))
      (node (ref "U4") (pin "22") (pinfunction "CH9_22") (pintype "bidirectional"))
    )
    (net (code "78") (name "/EO7") (class "Default")
      (node (ref "IC15") (pin "1") (pinfunction "OUT_1") (pintype "output"))
      (node (ref "R50") (pin "2") (pinfunction "2_2") (pintype "passive"))
      (node (ref "U4") (pin "21") (pinfunction "CH10_21") (pintype "bidirectional"))
    )
    (net (code "79") (name "/EO8") (class "Default")
      (node (ref "IC15") (pin "7") (pinfunction "OUT_7") (pintype "output"))
      (node (ref "R53") (pin "2") (pinfunction "2_2") (pintype "passive"))
      (node (ref "U4") (pin "20") (pinfunction "CH11_20") (pintype "bidirectional"))
    )
    (net (code "80") (name "/EO9") (class "Default")
      (node (ref "IC14") (pin "14") (pinfunction "OUT_14") (pintype "output"))
      (node (ref "R62") (pin "2") (pinfunction "2_2") (pintype "passive"))
      (node (ref "U4") (pin "6") (pinfunction "CH3_6") (pintype "bidirectional"))
    )
    (net (code "81") (name "/EO10") (class "Default")
      (node (ref "IC14") (pin "8") (pinfunction "OUT_8") (pintype "output"))
      (node (ref "R58") (pin "2") (pinfunction "2_2") (pintype "passive"))
      (node (ref "U4") (pin "7") (pinfunction "CH2_7") (pintype "bidirectional"))
    )
    (net (code "82") (name "/EO11") (class "Default")
      (node (ref "IC24") (pin "14") (pinfunction "OUT_14") (pintype "output"))
      (node (ref "R95") (pin "2") (pinfunction "2_2") (pintype "passive"))
      (node (ref "U4") (pin "8") (pinfunction "CH1_8") (pintype "bidirectional"))
    )
    (net (code "83") (name "/EO12") (class "Default")
      (node (ref "IC24") (pin "8") (pinfunction "OUT_8") (pintype "output"))
      (node (ref "R84") (pin "2") (pinfunction "2_2") (pintype "passive"))
      (node (ref "U4") (pin "9") (pinfunction "CH0_9") (pintype "bidirectional"))
    )
    (net (code "84") (name "/EO13") (class "Default")
      (node (ref "IC5") (pin "14") (pinfunction "OUT_14") (pintype "output"))
      (node (ref "R43") (pin "2") (pinfunction "2_2") (pintype "passive"))
      (node (ref "U4") (pin "19") (pinfunction "CH12_19") (pintype "bidirectional"))
    )
    (net (code "85") (name "/EO14") (class "Default")
      (node (ref "IC5") (pin "8") (pinfunction "OUT_8") (pintype "output"))
      (node (ref "R33") (pin "2") (pinfunction "2_2") (pintype "passive"))
      (node (ref "U4") (pin "18") (pinfunction "CH13_18") (pintype "bidirectional"))
    )
    (net (code "86") (name "/EO15") (class "Default")
      (node (ref "IC15") (pin "14") (pinfunction "OUT_14") (pintype "output"))
      (node (ref "R63") (pin "2") (pinfunction "2_2") (pintype "passive"))
      (node (ref "U4") (pin "17") (pinfunction "CH14_17") (pintype "bidirectional"))
    )
    (net (code "87") (name "/EO16") (class "Default")
      (node (ref "IC15") (pin "8") (pinfunction "OUT_8") (pintype "output"))
      (node (ref "R56") (pin "2") (pinfunction "2_2") (pintype "passive"))
      (node (ref "U4") (pin "16") (pinfunction "CH15_16") (pintype "bidirectional"))
    )
    (net (code "88") (name "/FO1") (class "Default")
      (node (ref "IC22") (pin "1") (pinfunction "OUT_1") (pintype "output"))
      (node (ref "R68") (pin "2") (pinfunction "2_2") (pintype "passive"))
      (node (ref "U6") (pin "2") (pinfunction "CH7_2") (pintype "bidirectional"))
    )
    (net (code "89") (name "/FO2") (class "Default")
      (node (ref "IC22") (pin "7") (pinfunction "OUT_7") (pintype "output"))
      (node (ref "R79") (pin "2") (pinfunction "2_2") (pintype "passive"))
      (node (ref "U6") (pin "3") (pinfunction "CH6_3") (pintype "bidirectional"))
    )
    (net (code "90") (name "/FO3") (class "Default")
      (node (ref "IC3") (pin "1") (pinfunction "OUT_1") (pintype "output"))
      (node (ref "R2") (pin "2") (pinfunction "2_2") (pintype "passive"))
      (node (ref "U6") (pin "4") (pinfunction "CH5_4") (pintype "bidirectional"))
    )
    (net (code "91") (name "/FO4") (class "Default")
      (node (ref "IC3") (pin "7") (pinfunction "OUT_7") (pintype "output"))
      (node (ref "R17") (pin "2") (pinfunction "2_2") (pintype "passive"))
      (node (ref "U6") (pin "5") (pinfunction "CH4_5") (pintype "bidirectional"))
    )
    (net (code "92") (name "/FO5") (class "Default")
      (node (ref "IC9") (pin "1") (pinfunction "OUT_1") (pintype "output"))
      (node (ref "R10") (pin "2") (pinfunction "2_2") (pintype "passive"))
      (node (ref "U6") (pin "23") (pinfunction "CH8_23") (pintype "bidirectional"))
    )
    (net (code "93") (name "/FO6") (class "Default")
      (node (ref "IC9") (pin "7") (pinfunction "OUT_7") (pintype "output"))
      (node (ref "R21") (pin "2") (pinfunction "2_2") (pintype "passive"))
      (node (ref "U6") (pin "22") (pinfunction "CH9_22") (pintype "bidirectional"))
    )
    (net (code "94") (name "/FO7") (class "Default")
      (node (ref "IC21") (pin "1") (pinfunction "OUT_1") (pintype "output"))
      (node (ref "R73") (pin "2") (pinfunction "2_2") (pintype "passive"))
      (node (ref "U6") (pin "21") (pinfunction "CH10_21") (pintype "bidirectional"))
    )
    (net (code "95") (name "/FO8") (class "Default")
      (node (ref "IC21") (pin "7") (pinfunction "OUT_7") (pintype "output"))
      (node (ref "R81") (pin "2") (pinfunction "2_2") (pintype "passive"))
      (node (ref "U6") (pin "20") (pinfunction "CH11_20") (pintype "bidirectional"))
    )
    (net (code "96") (name "/FO9") (class "Default")
      (node (ref "IC22") (pin "14") (pinfunction "OUT_14") (pintype "output"))
      (node (ref "R93") (pin "2") (pinfunction "2_2") (pintype "passive"))
      (node (ref "U6") (pin "6") (pinfunction "CH3_6") (pintype "bidirectional"))
    )
    (net (code "97") (name "/FO10") (class "Default")
      (node (ref "IC22") (pin "8") (pinfunction "OUT_8") (pintype "output"))
      (node (ref "R88") (pin "2") (pinfunction "2_2") (pintype "passive"))
      (node (ref "U6") (pin "7") (pinfunction "CH2_7") (pintype "bidirectional"))
    )
    (net (code "98") (name "/FO11") (class "Default")
      (node (ref "IC3") (pin "14") (pinfunction "OUT_14") (pintype "output"))
      (node (ref "R45") (pin "2") (pinfunction "2_2") (pintype "passive"))
      (node (ref "U6") (pin "8") (pinfunction "CH1_8") (pintype "bidirectional"))
    )
    (net (code "99") (name "/FO12") (class "Default")
      (node (ref "IC3") (pin "8") (pinfunction "OUT_8") (pintype "output"))
      (node (ref "R34") (pin "2") (pinfunction "2_2") (pintype "passive"))
      (node (ref "U6") (pin "9") (pinfunction "CH0_9") (pintype "bidirectional"))
    )
    (net (code "100") (name "/FO13") (class "Default")
      (node (ref "IC9") (pin "14") (pinfunction "OUT_14") (pintype "output"))
      (node (ref "R37") (pin "2") (pinfunction "2_2") (pintype "passive"))
      (node (ref "U6") (pin "19") (pinfunction "CH12_19") (pintype "bidirectional"))
    )
    (net (code "101") (name "/FO14") (class "Default")
      (node (ref "IC9") (pin "8") (pinfunction "OUT_8") (pintype "output"))
      (node (ref "R28") (pin "2") (pinfunction "2_2") (pintype "passive"))
      (node (ref "U6") (pin "18") (pinfunction "CH13_18") (pintype "bidirectional"))
    )
    (net (code "102") (name "/FO15") (class "Default")
      (node (ref "IC21") (pin "14") (pinfunction "OUT_14") (pintype "output"))
      (node (ref "R97") (pin "2") (pinfunction "2_2") (pintype "passive"))
      (node (ref "U6") (pin "17") (pinfunction "CH14_17") (pintype "bidirectional"))
    )
    (net (code "103") (name "/FO16") (class "Default")
      (node (ref "IC21") (pin "8") (pinfunction "OUT_8") (pintype "output"))
      (node (ref "R89") (pin "2") (pinfunction "2_2") (pintype "passive"))
      (node (ref "U6") (pin "16") (pinfunction "CH15_16") (pintype "bidirectional"))
    )
    (net (code "104") (name "/PD1") (class "Default")
      (node (ref "IC10") (pin "2") (pinfunction "-IN_2") (pintype "input"))
      (node (ref "PHD1") (pin "3") (pinfunction "2_3") (pintype "bidirectional"))
      (node (ref "PHD1") (pin "4") (pinfunction "2_4") (pintype "bidirectional"))
      (node (ref "R11") (pin "1") (pinfunction "1_1") (pintype "passive"))
    )
    (net (code "105") (name "/PD2") (class "Default")
      (node (ref "IC10") (pin "6") (pinfunction "-IN_6") (pintype "input"))
      (node (ref "PHD2") (pin "3") (pinfunction "2_3") (pintype "bidirectional"))
      (node (ref "PHD2") (pin "4") (pinfunction "2_4") (pintype "bidirectional"))
      (node (ref "R22") (pin "1") (pinfunction "1_1") (pintype "passive"))
    )
    (net (code "106") (name "/PD3") (class "Default")
      (node (ref "IC11") (pin "2") (pinfunction "-IN_2") (pintype "input"))
      (node (ref "PHD3") (pin "3") (pinfunction "2_3") (pintype "bidirectional"))
      (node (ref "PHD3") (pin "4") (pinfunction "2_4") (pintype "bidirectional"))
      (node (ref "R12") (pin "1") (pinfunction "1_1") (pintype "passive"))
    )
    (net (code "107") (name "/PD4") (class "Default")
      (node (ref "IC11") (pin "6") (pinfunction "-IN_6") (pintype "input"))
      (node (ref "PHD4") (pin "3") (pinfunction "2_3") (pintype "bidirectional"))
      (node (ref "PHD4") (pin "4") (pinfunction "2_4") (pintype "bidirectional"))
      (node (ref "R23") (pin "1") (pinfunction "1_1") (pintype "passive"))
    )
    (net (code "108") (name "/PD5") (class "Default")
      (node (ref "IC8") (pin "2") (pinfunction "-IN_2") (pintype "input"))
      (node (ref "PHD5") (pin "3") (pinfunction "2_3") (pintype "bidirectional"))
      (node (ref "PHD5") (pin "4") (pinfunction "2_4") (pintype "bidirectional"))
      (node (ref "R9") (pin "1") (pinfunction "1_1") (pintype "passive"))
    )
    (net (code "109") (name "/PD6") (class "Default")
      (node (ref "IC8") (pin "6") (pinfunction "-IN_6") (pintype "input"))
      (node (ref "PHD6") (pin "3") (pinfunction "2_3") (pintype "bidirectional"))
      (node (ref "PHD6") (pin "4") (pinfunction "2_4") (pintype "bidirectional"))
      (node (ref "R20") (pin "1") (pinfunction "1_1") (pintype "passive"))
    )
    (net (code "110") (name "/PD7") (class "Default")
      (node (ref "IC7") (pin "2") (pinfunction "-IN_2") (pintype "input"))
      (node (ref "PHD7") (pin "3") (pinfunction "2_3") (pintype "bidirectional"))
      (node (ref "PHD7") (pin "4") (pinfunction "2_4") (pintype "bidirectional"))
      (node (ref "R8") (pin "1") (pinfunction "1_1") (pintype "passive"))
    )
    (net (code "111") (name "/PD8") (class "Default")
      (node (ref "IC7") (pin "6") (pinfunction "-IN_6") (pintype "input"))
      (node (ref "PHD8") (pin "3") (pinfunction "2_3") (pintype "bidirectional"))
      (node (ref "PHD8") (pin "4") (pinfunction "2_4") (pintype "bidirectional"))
      (node (ref "R19") (pin "1") (pinfunction "1_1") (pintype "passive"))
    )
    (net (code "112") (name "/PD9") (class "Default")
      (node (ref "IC10") (pin "13") (pinfunction "-IN_13") (pintype "input"))
      (node (ref "PHD9") (pin "3") (pinfunction "2_3") (pintype "bidirectional"))
      (node (ref "PHD9") (pin "4") (pinfunction "2_4") (pintype "bidirectional"))
      (node (ref "R38") (pin "1") (pinfunction "1_1") (pintype "passive"))
    )
    (net (code "113") (name "/PD10") (class "Default")
      (node (ref "IC10") (pin "9") (pinfunction "-IN_9") (pintype "input"))
      (node (ref "PHD10") (pin "3") (pinfunction "2_3") (pintype "bidirectional"))
      (node (ref "PHD10") (pin "4") (pinfunction "2_4") (pintype "bidirectional"))
      (node (ref "R30") (pin "1") (pinfunction "1_1") (pintype "passive"))
    )
    (net (code "114") (name "/PD11") (class "Default")
      (node (ref "IC11") (pin "13") (pinfunction "-IN_13") (pintype "input"))
      (node (ref "PHD11") (pin "3") (pinfunction "2_3") (pintype "bidirectional"))
      (node (ref "PHD11") (pin "4") (pinfunction "2_4") (pintype "bidirectional"))
      (node (ref "R39") (pin "1") (pinfunction "1_1") (pintype "passive"))
    )
    (net (code "115") (name "/PD12") (class "Default")
      (node (ref "IC11") (pin "9") (pinfunction "-IN_9") (pintype "input"))
      (node (ref "PHD12") (pin "3") (pinfunction "2_3") (pintype "bidirectional"))
      (node (ref "PHD12") (pin "4") (pinfunction "2_4") (pintype "bidirectional"))
      (node (ref "R31") (pin "1") (pinfunction "1_1") (pintype "passive"))
    )
    (net (code "116") (name "/PD13") (class "Default")
      (node (ref "IC8") (pin "13") (pinfunction "-IN_13") (pintype "input"))
      (node (ref "PHD13") (pin "3") (pinfunction "2_3") (pintype "bidirectional"))
      (node (ref "PHD13") (pin "4") (pinfunction "2_4") (pintype "bidirectional"))
      (node (ref "R36") (pin "1") (pinfunction "1_1") (pintype "passive"))
    )
    (net (code "117") (name "/PD14") (class "Default")
      (node (ref "IC8") (pin "9") (pinfunction "-IN_9") (pintype "input"))
      (node (ref "PHD14") (pin "3") (pinfunction "2_3") (pintype "bidirectional"))
      (node (ref "PHD14") (pin "4") (pinfunction "2_4") (pintype "bidirectional"))
      (node (ref "R27") (pin "1") (pinfunction "1_1") (pintype "passive"))
    )
    (net (code "118") (name "/PD15") (class "Default")
      (node (ref "IC7") (pin "13") (pinfunction "-IN_13") (pintype "input"))
      (node (ref "PHD15") (pin "3") (pinfunction "2_3") (pintype "bidirectional"))
      (node (ref "PHD15") (pin "4") (pinfunction "2_4") (pintype "bidirectional"))
      (node (ref "R35") (pin "1") (pinfunction "1_1") (pintype "passive"))
    )
    (net (code "119") (name "/PD16") (class "Default")
      (node (ref "IC7") (pin "9") (pinfunction "-IN_9") (pintype "input"))
      (node (ref "PHD16") (pin "3") (pinfunction "2_3") (pintype "bidirectional"))
      (node (ref "PHD16") (pin "4") (pinfunction "2_4") (pintype "bidirectional"))
      (node (ref "R26") (pin "1") (pinfunction "1_1") (pintype "passive"))
    )
    (net (code "120") (name "/PD17") (class "Default")
      (node (ref "IC17") (pin "2") (pinfunction "-IN_2") (pintype "input"))
      (node (ref "PHD17") (pin "3") (pinfunction "2_3") (pintype "bidirectional"))
      (node (ref "PHD17") (pin "4") (pinfunction "2_4") (pintype "bidirectional"))
      (node (ref "R66") (pin "1") (pinfunction "1_1") (pintype "passive"))
    )
    (net (code "121") (name "/PD18") (class "Default")
      (node (ref "IC17") (pin "6") (pinfunction "-IN_6") (pintype "input"))
      (node (ref "PHD18") (pin "3") (pinfunction "2_3") (pintype "bidirectional"))
      (node (ref "PHD18") (pin "4") (pinfunction "2_4") (pintype "bidirectional"))
      (node (ref "R77") (pin "1") (pinfunction "1_1") (pintype "passive"))
    )
    (net (code "122") (name "/PD19") (class "Default")
      (node (ref "IC20") (pin "2") (pinfunction "-IN_2") (pintype "input"))
      (node (ref "PHD19") (pin "3") (pinfunction "2_3") (pintype "bidirectional"))
      (node (ref "PHD19") (pin "4") (pinfunction "2_4") (pintype "bidirectional"))
      (node (ref "R70") (pin "1") (pinfunction "1_1") (pintype "passive"))
    )
    (net (code "123") (name "/PD20") (class "Default")
      (node (ref "IC20") (pin "6") (pinfunction "-IN_6") (pintype "input"))
      (node (ref "PHD20") (pin "3") (pinfunction "2_3") (pintype "bidirectional"))
      (node (ref "PHD20") (pin "4") (pinfunction "2_4") (pintype "bidirectional"))
      (node (ref "R80") (pin "1") (pinfunction "1_1") (pintype "passive"))
    )
    (net (code "124") (name "/PD21") (class "Default")
      (node (ref "IC2") (pin "2") (pinfunction "-IN_2") (pintype "input"))
      (node (ref "PHD21") (pin "3") (pinfunction "2_3") (pintype "bidirectional"))
      (node (ref "PHD21") (pin "4") (pinfunction "2_4") (pintype "bidirectional"))
      (node (ref "R5") (pin "1") (pinfunction "1_1") (pintype "passive"))
    )
    (net (code "125") (name "/PD22") (class "Default")
      (node (ref "IC2") (pin "6") (pinfunction "-IN_6") (pintype "input"))
      (node (ref "PHD22") (pin "3") (pinfunction "2_3") (pintype "bidirectional"))
      (node (ref "PHD22") (pin "4") (pinfunction "2_4") (pintype "bidirectional"))
      (node (ref "R18") (pin "1") (pinfunction "1_1") (pintype "passive"))
    )
    (net (code "126") (name "/PD23") (class "Default")
      (node (ref "IC1") (pin "2") (pinfunction "-IN_2") (pintype "input"))
      (node (ref "PHD23") (pin "3") (pinfunction "2_3") (pintype "bidirectional"))
      (node (ref "PHD23") (pin "4") (pinfunction "2_4") (pintype "bidirectional"))
      (node (ref "R4") (pin "1") (pinfunction "1_1") (pintype "passive"))
    )
    (net (code "127") (name "/PD24") (class "Default")
      (node (ref "IC1") (pin "6") (pinfunction "-IN_6") (pintype "input"))
      (node (ref "PHD24") (pin "3") (pinfunction "2_3") (pintype "bidirectional"))
      (node (ref "PHD24") (pin "4") (pinfunction "2_4") (pintype "bidirectional"))
      (node (ref "R15") (pin "1") (pinfunction "1_1") (pintype "passive"))
    )
    (net (code "128") (name "/PD25") (class "Default")
      (node (ref "IC17") (pin "13") (pinfunction "-IN_13") (pintype "input"))
      (node (ref "PHD25") (pin "3") (pinfunction "2_3") (pintype "bidirectional"))
      (node (ref "PHD25") (pin "4") (pinfunction "2_4") (pintype "bidirectional"))
      (node (ref "R90") (pin "1") (pinfunction "1_1") (pintype "passive"))
    )
    (net (code "129") (name "/PD26") (class "Default")
      (node (ref "IC17") (pin "9") (pinfunction "-IN_9") (pintype "input"))
      (node (ref "PHD26") (pin "3") (pinfunction "2_3") (pintype "bidirectional"))
      (node (ref "PHD26") (pin "4") (pinfunction "2_4") (pintype "bidirectional"))
      (node (ref "R83") (pin "1") (pinfunction "1_1") (pintype "passive"))
    )
    (net (code "130") (name "/PD27") (class "Default")
      (node (ref "IC20") (pin "13") (pinfunction "-IN_13") (pintype "input"))
      (node (ref "PHD27") (pin "3") (pinfunction "2_3") (pintype "bidirectional"))
      (node (ref "PHD27") (pin "4") (pinfunction "2_4") (pintype "bidirectional"))
      (node (ref "R96") (pin "1") (pinfunction "1_1") (pintype "passive"))
    )
    (net (code "131") (name "/PD28") (class "Default")
      (node (ref "IC20") (pin "9") (pinfunction "-IN_9") (pintype "input"))
      (node (ref "PHD28") (pin "3") (pinfunction "2_3") (pintype "bidirectional"))
      (node (ref "PHD28") (pin "4") (pinfunction "2_4") (pintype "bidirectional"))
      (node (ref "R87") (pin "1") (pinfunction "1_1") (pintype "passive"))
    )
    (net (code "132") (name "/PD29") (class "Default")
      (node (ref "IC2") (pin "13") (pinfunction "-IN_13") (pintype "input"))
      (node (ref "PHD29") (pin "3") (pinfunction "2_3") (pintype "bidirectional"))
      (node (ref "PHD29") (pin "4") (pinfunction "2_4") (pintype "bidirectional"))
      (node (ref "R41") (pin "1") (pinfunction "1_1") (pintype "passive"))
    )
    (net (code "133") (name "/PD30") (class "Default")
      (node (ref "IC2") (pin "9") (pinfunction "-IN_9") (pintype "input"))
      (node (ref "PHD30") (pin "3") (pinfunction "2_3") (pintype "bidirectional"))
      (node (ref "PHD30") (pin "4") (pinfunction "2_4") (pintype "bidirectional"))
      (node (ref "R24") (pin "1") (pinfunction "1_1") (pintype "passive"))
    )
    (net (code "134") (name "/PD31") (class "Default")
      (node (ref "IC1") (pin "13") (pinfunction "-IN_13") (pintype "input"))
      (node (ref "PHD31") (pin "3") (pinfunction "2_3") (pintype "bidirectional"))
      (node (ref "PHD31") (pin "4") (pinfunction "2_4") (pintype "bidirectional"))
      (node (ref "R44") (pin "1") (pinfunction "1_1") (pintype "passive"))
    )
    (net (code "135") (name "/PD32") (class "Default")
      (node (ref "IC1") (pin "9") (pinfunction "-IN_9") (pintype "input"))
      (node (ref "PHD32") (pin "3") (pinfunction "2_3") (pintype "bidirectional"))
      (node (ref "PHD32") (pin "4") (pinfunction "2_4") (pintype "bidirectional"))
      (node (ref "R25") (pin "1") (pinfunction "1_1") (pintype "passive"))
    )
    (net (code "136") (name "/PD33") (class "Default")
      (node (ref "IC13") (pin "2") (pinfunction "-IN_2") (pintype "input"))
      (node (ref "PHD33") (pin "3") (pinfunction "2_3") (pintype "bidirectional"))
      (node (ref "PHD33") (pin "4") (pinfunction "2_4") (pintype "bidirectional"))
      (node (ref "R49") (pin "1") (pinfunction "1_1") (pintype "passive"))
    )
    (net (code "137") (name "/PD34") (class "Default")
      (node (ref "IC13") (pin "6") (pinfunction "-IN_6") (pintype "input"))
      (node (ref "PHD34") (pin "3") (pinfunction "2_3") (pintype "bidirectional"))
      (node (ref "PHD34") (pin "4") (pinfunction "2_4") (pintype "bidirectional"))
      (node (ref "R55") (pin "1") (pinfunction "1_1") (pintype "passive"))
    )
    (net (code "138") (name "/PD35") (class "Default")
      (node (ref "IC12") (pin "2") (pinfunction "-IN_2") (pintype "input"))
      (node (ref "PHD35") (pin "3") (pinfunction "2_3") (pintype "bidirectional"))
      (node (ref "PHD35") (pin "4") (pinfunction "2_4") (pintype "bidirectional"))
      (node (ref "R48") (pin "1") (pinfunction "1_1") (pintype "passive"))
    )
    (net (code "139") (name "/PD36") (class "Default")
      (node (ref "IC12") (pin "6") (pinfunction "-IN_6") (pintype "input"))
      (node (ref "PHD36") (pin "3") (pinfunction "2_3") (pintype "bidirectional"))
      (node (ref "PHD36") (pin "4") (pinfunction "2_4") (pintype "bidirectional"))
      (node (ref "R54") (pin "1") (pinfunction "1_1") (pintype "passive"))
    )
    (net (code "140") (name "/PD37") (class "Default")
      (node (ref "IC23") (pin "2") (pinfunction "-IN_2") (pintype "input"))
      (node (ref "PHD37") (pin "3") (pinfunction "2_3") (pintype "bidirectional"))
      (node (ref "PHD37") (pin "4") (pinfunction "2_4") (pintype "bidirectional"))
      (node (ref "R72") (pin "1") (pinfunction "1_1") (pintype "passive"))
    )
    (net (code "141") (name "/PD38") (class "Default")
      (node (ref "IC23") (pin "6") (pinfunction "-IN_6") (pintype "input"))
      (node (ref "PHD38") (pin "3") (pinfunction "2_3") (pintype "bidirectional"))
      (node (ref "PHD38") (pin "4") (pinfunction "2_4") (pintype "bidirectional"))
      (node (ref "R76") (pin "1") (pinfunction "1_1") (pintype "passive"))
    )
    (net (code "142") (name "/PD39") (class "Default")
      (node (ref "IC19") (pin "2") (pinfunction "-IN_2") (pintype "input"))
      (node (ref "PHD39") (pin "3") (pinfunction "2_3") (pintype "bidirectional"))
      (node (ref "PHD39") (pin "4") (pinfunction "2_4") (pintype "bidirectional"))
      (node (ref "R71") (pin "1") (pinfunction "1_1") (pintype "passive"))
    )
    (net (code "143") (name "/PD40") (class "Default")
      (node (ref "IC19") (pin "6") (pinfunction "-IN_6") (pintype "input"))
      (node (ref "PHD40") (pin "3") (pinfunction "2_3") (pintype "bidirectional"))
      (node (ref "PHD40") (pin "4") (pinfunction "2_4") (pintype "bidirectional"))
      (node (ref "R75") (pin "1") (pinfunction "1_1") (pintype "passive"))
    )
    (net (code "144") (name "/PD41") (class "Default")
      (node (ref "IC13") (pin "13") (pinfunction "-IN_13") (pintype "input"))
      (node (ref "PHD41") (pin "3") (pinfunction "2_3") (pintype "bidirectional"))
      (node (ref "PHD41") (pin "4") (pinfunction "2_4") (pintype "bidirectional"))
      (node (ref "R65") (pin "1") (pinfunction "1_1") (pintype "passive"))
    )
    (net (code "145") (name "/PD42") (class "Default")
      (node (ref "IC13") (pin "9") (pinfunction "-IN_9") (pintype "input"))
      (node (ref "PHD42") (pin "3") (pinfunction "2_3") (pintype "bidirectional"))
      (node (ref "PHD42") (pin "4") (pinfunction "2_4") (pintype "bidirectional"))
      (node (ref "R60") (pin "1") (pinfunction "1_1") (pintype "passive"))
    )
    (net (code "146") (name "/PD43") (class "Default")
      (node (ref "IC12") (pin "13") (pinfunction "-IN_13") (pintype "input"))
      (node (ref "PHD43") (pin "3") (pinfunction "2_3") (pintype "bidirectional"))
      (node (ref "PHD43") (pin "4") (pinfunction "2_4") (pintype "bidirectional"))
      (node (ref "R64") (pin "1") (pinfunction "1_1") (pintype "passive"))
    )
    (net (code "147") (name "/PD44") (class "Default")
      (node (ref "IC12") (pin "9") (pinfunction "-IN_9") (pintype "input"))
      (node (ref "PHD44") (pin "3") (pinfunction "2_3") (pintype "bidirectional"))
      (node (ref "PHD44") (pin "4") (pinfunction "2_4") (pintype "bidirectional"))
      (node (ref "R59") (pin "1") (pinfunction "1_1") (pintype "passive"))
    )
    (net (code "148") (name "/PD45") (class "Default")
      (node (ref "IC23") (pin "13") (pinfunction "-IN_13") (pintype "input"))
      (node (ref "PHD45") (pin "3") (pinfunction "2_3") (pintype "bidirectional"))
      (node (ref "PHD45") (pin "4") (pinfunction "2_4") (pintype "bidirectional"))
      (node (ref "R94") (pin "1") (pinfunction "1_1") (pintype "passive"))
    )
    (net (code "149") (name "/PD46") (class "Default")
      (node (ref "IC23") (pin "9") (pinfunction "-IN_9") (pintype "input"))
      (node (ref "PHD46") (pin "3") (pinfunction "2_3") (pintype "bidirectional"))
      (node (ref "PHD46") (pin "4") (pinfunction "2_4") (pintype "bidirectional"))
      (node (ref "R82") (pin "1") (pinfunction "1_1") (pintype "passive"))
    )
    (net (code "150") (name "/PD47") (class "Default")
      (node (ref "IC19") (pin "13") (pinfunction "-IN_13") (pintype "input"))
      (node (ref "PHD47") (pin "3") (pinfunction "2_3") (pintype "bidirectional"))
      (node (ref "PHD47") (pin "4") (pinfunction "2_4") (pintype "bidirectional"))
      (node (ref "R92") (pin "1") (pinfunction "1_1") (pintype "passive"))
    )
    (net (code "151") (name "/PD48") (class "Default")
      (node (ref "IC19") (pin "9") (pinfunction "-IN_9") (pintype "input"))
      (node (ref "PHD48") (pin "3") (pinfunction "2_3") (pintype "bidirectional"))
      (node (ref "PHD48") (pin "4") (pinfunction "2_4") (pintype "bidirectional"))
      (node (ref "R86") (pin "1") (pinfunction "1_1") (pintype "passive"))
    )
    (net (code "152") (name "/PD49") (class "Default")
      (node (ref "IC6") (pin "2") (pinfunction "-IN_2") (pintype "input"))
      (node (ref "PHD49") (pin "3") (pinfunction "2_3") (pintype "bidirectional"))
      (node (ref "PHD49") (pin "4") (pinfunction "2_4") (pintype "bidirectional"))
      (node (ref "R1") (pin "1") (pinfunction "1_1") (pintype "passive"))
    )
    (net (code "153") (name "/PD50") (class "Default")
      (node (ref "IC6") (pin "6") (pinfunction "-IN_6") (pintype "input"))
      (node (ref "PHD50") (pin "3") (pinfunction "2_3") (pintype "bidirectional"))
      (node (ref "PHD50") (pin "4") (pinfunction "2_4") (pintype "bidirectional"))
      (node (ref "R14") (pin "1") (pinfunction "1_1") (pintype "passive"))
    )
    (net (code "154") (name "/PD51") (class "Default")
      (node (ref "IC16") (pin "2") (pinfunction "-IN_2") (pintype "input"))
      (node (ref "PHD51") (pin "3") (pinfunction "2_3") (pintype "bidirectional"))
      (node (ref "PHD51") (pin "4") (pinfunction "2_4") (pintype "bidirectional"))
      (node (ref "R47") (pin "1") (pinfunction "1_1") (pintype "passive"))
    )
    (net (code "155") (name "/PD52") (class "Default")
      (node (ref "IC16") (pin "6") (pinfunction "-IN_6") (pintype "input"))
      (node (ref "PHD52") (pin "3") (pinfunction "2_3") (pintype "bidirectional"))
      (node (ref "PHD52") (pin "4") (pinfunction "2_4") (pintype "bidirectional"))
      (node (ref "R51") (pin "1") (pinfunction "1_1") (pintype "passive"))
    )
    (net (code "156") (name "/PD53") (class "Default")
      (node (ref "IC18") (pin "2") (pinfunction "-IN_2") (pintype "input"))
      (node (ref "PHD53") (pin "3") (pinfunction "2_3") (pintype "bidirectional"))
      (node (ref "PHD53") (pin "4") (pinfunction "2_4") (pintype "bidirectional"))
      (node (ref "R69") (pin "1") (pinfunction "1_1") (pintype "passive"))
    )
    (net (code "157") (name "/PD54") (class "Default")
      (node (ref "IC18") (pin "6") (pinfunction "-IN_6") (pintype "input"))
      (node (ref "PHD54") (pin "3") (pinfunction "2_3") (pintype "bidirectional"))
      (node (ref "PHD54") (pin "4") (pinfunction "2_4") (pintype "bidirectional"))
      (node (ref "R74") (pin "1") (pinfunction "1_1") (pintype "passive"))
    )
    (net (code "158") (name "/PD55") (class "Default")
      (node (ref "IC4") (pin "2") (pinfunction "-IN_2") (pintype "input"))
      (node (ref "PHD55") (pin "3") (pinfunction "2_3") (pintype "bidirectional"))
      (node (ref "PHD55") (pin "4") (pinfunction "2_4") (pintype "bidirectional"))
      (node (ref "R3") (pin "1") (pinfunction "1_1") (pintype "passive"))
    )
    (net (code "159") (name "/PD56") (class "Default")
      (node (ref "IC4") (pin "6") (pinfunction "-IN_6") (pintype "input"))
      (node (ref "PHD56") (pin "3") (pinfunction "2_3") (pintype "bidirectional"))
      (node (ref "PHD56") (pin "4") (pinfunction "2_4") (pintype "bidirectional"))
      (node (ref "R16") (pin "1") (pinfunction "1_1") (pintype "passive"))
    )
    (net (code "160") (name "/PD57") (class "Default")
      (node (ref "IC6") (pin "13") (pinfunction "-IN_13") (pintype "input"))
      (node (ref "PHD57") (pin "3") (pinfunction "2_3") (pintype "bidirectional"))
      (node (ref "PHD57") (pin "4") (pinfunction "2_4") (pintype "bidirectional"))
      (node (ref "R42") (pin "1") (pinfunction "1_1") (pintype "passive"))
    )
    (net (code "161") (name "/PD58") (class "Default")
      (node (ref "IC6") (pin "9") (pinfunction "-IN_9") (pintype "input"))
      (node (ref "PHD58") (pin "3") (pinfunction "2_3") (pintype "bidirectional"))
      (node (ref "PHD58") (pin "4") (pinfunction "2_4") (pintype "bidirectional"))
      (node (ref "R29") (pin "1") (pinfunction "1_1") (pintype "passive"))
    )
    (net (code "162") (name "/PD59") (class "Default")
      (node (ref "IC16") (pin "13") (pinfunction "-IN_13") (pintype "input"))
      (node (ref "PHD59") (pin "3") (pinfunction "2_3") (pintype "bidirectional"))
      (node (ref "PHD59") (pin "4") (pinfunction "2_4") (pintype "bidirectional"))
      (node (ref "R61") (pin "1") (pinfunction "1_1") (pintype "passive"))
    )
    (net (code "163") (name "/PD60") (class "Default")
      (node (ref "IC16") (pin "9") (pinfunction "-IN_9") (pintype "input"))
      (node (ref "PHD60") (pin "3") (pinfunction "2_3") (pintype "bidirectional"))
      (node (ref "PHD60") (pin "4") (pinfunction "2_4") (pintype "bidirectional"))
      (node (ref "R57") (pin "1") (pinfunction "1_1") (pintype "passive"))
    )
    (net (code "164") (name "/PD61") (class "Default")
      (node (ref "IC18") (pin "13") (pinfunction "-IN_13") (pintype "input"))
      (node (ref "PHD61") (pin "3") (pinfunction "2_3") (pintype "bidirectional"))
      (node (ref "PHD61") (pin "4") (pinfunction "2_4") (pintype "bidirectional"))
      (node (ref "R91") (pin "1") (pinfunction "1_1") (pintype "passive"))
    )
    (net (code "165") (name "/PD62") (class "Default")
      (node (ref "IC18") (pin "9") (pinfunction "-IN_9") (pintype "input"))
      (node (ref "PHD62") (pin "3") (pinfunction "2_3") (pintype "bidirectional"))
      (node (ref "PHD62") (pin "4") (pinfunction "2_4") (pintype "bidirectional"))
      (node (ref "R85") (pin "1") (pinfunction "1_1") (pintype "passive"))
    )
    (net (code "166") (name "/PD63") (class "Default")
      (node (ref "IC4") (pin "13") (pinfunction "-IN_13") (pintype "input"))
      (node (ref "PHD63") (pin "3") (pinfunction "2_3") (pintype "bidirectional"))
      (node (ref "PHD63") (pin "4") (pinfunction "2_4") (pintype "bidirectional"))
      (node (ref "R40") (pin "1") (pinfunction "1_1") (pintype "passive"))
    )
    (net (code "167") (name "/PD64") (class "Default")
      (node (ref "IC4") (pin "9") (pinfunction "-IN_9") (pintype "input"))
      (node (ref "PHD64") (pin "3") (pinfunction "2_3") (pintype "bidirectional"))
      (node (ref "PHD64") (pin "4") (pinfunction "2_4") (pintype "bidirectional"))
      (node (ref "R32") (pin "1") (pinfunction "1_1") (pintype "passive"))
    )
    (net (code "168") (name "/PD65") (class "Default")
      (node (ref "IC14") (pin "2") (pinfunction "-IN_2") (pintype "input"))
      (node (ref "PHD65") (pin "3") (pinfunction "2_3") (pintype "bidirectional"))
      (node (ref "PHD65") (pin "4") (pinfunction "2_4") (pintype "bidirectional"))
      (node (ref "R46") (pin "1") (pinfunction "1_1") (pintype "passive"))
    )
    (net (code "169") (name "/PD66") (class "Default")
      (node (ref "IC14") (pin "6") (pinfunction "-IN_6") (pintype "input"))
      (node (ref "PHD66") (pin "3") (pinfunction "2_3") (pintype "bidirectional"))
      (node (ref "PHD66") (pin "4") (pinfunction "2_4") (pintype "bidirectional"))
      (node (ref "R52") (pin "1") (pinfunction "1_1") (pintype "passive"))
    )
    (net (code "170") (name "/PD67") (class "Default")
      (node (ref "IC24") (pin "2") (pinfunction "-IN_2") (pintype "input"))
      (node (ref "PHD67") (pin "3") (pinfunction "2_3") (pintype "bidirectional"))
      (node (ref "PHD67") (pin "4") (pinfunction "2_4") (pintype "bidirectional"))
      (node (ref "R67") (pin "1") (pinfunction "1_1") (pintype "passive"))
    )
    (net (code "171") (name "/PD68") (class "Default")
      (node (ref "IC24") (pin "6") (pinfunction "-IN_6") (pintype "input"))
      (node (ref "PHD68") (pin "3") (pinfunction "2_3") (pintype "bidirectional"))
      (node (ref "PHD68") (pin "4") (pinfunction "2_4") (pintype "bidirectional"))
      (node (ref "R78") (pin "1") (pinfunction "1_1") (pintype "passive"))
    )
    (net (code "172") (name "/PD69") (class "Default")
      (node (ref "IC5") (pin "2") (pinfunction "-IN_2") (pintype "input"))
      (node (ref "PHD69") (pin "3") (pinfunction "2_3") (pintype "bidirectional"))
      (node (ref "PHD69") (pin "4") (pinfunction "2_4") (pintype "bidirectional"))
      (node (ref "R7") (pin "1") (pinfunction "1_1") (pintype "passive"))
    )
    (net (code "173") (name "/PD70") (class "Default")
      (node (ref "IC5") (pin "6") (pinfunction "-IN_6") (pintype "input"))
      (node (ref "PHD70") (pin "3") (pinfunction "2_3") (pintype "bidirectional"))
      (node (ref "PHD70") (pin "4") (pinfunction "2_4") (pintype "bidirectional"))
      (node (ref "R13") (pin "1") (pinfunction "1_1") (pintype "passive"))
    )
    (net (code "174") (name "/PD71") (class "Default")
      (node (ref "IC15") (pin "2") (pinfunction "-IN_2") (pintype "input"))
      (node (ref "PHD71") (pin "3") (pinfunction "2_3") (pintype "bidirectional"))
      (node (ref "PHD71") (pin "4") (pinfunction "2_4") (pintype "bidirectional"))
      (node (ref "R50") (pin "1") (pinfunction "1_1") (pintype "passive"))
    )
    (net (code "175") (name "/PD72") (class "Default")
      (node (ref "IC15") (pin "6") (pinfunction "-IN_6") (pintype "input"))
      (node (ref "PHD72") (pin "3") (pinfunction "2_3") (pintype "bidirectional"))
      (node (ref "PHD72") (pin "4") (pinfunction "2_4") (pintype "bidirectional"))
      (node (ref "R53") (pin "1") (pinfunction "1_1") (pintype "passive"))
    )
    (net (code "176") (name "/PD73") (class "Default")
      (node (ref "IC14") (pin "13") (pinfunction "-IN_13") (pintype "input"))
      (node (ref "PHD73") (pin "3") (pinfunction "2_3") (pintype "bidirectional"))
      (node (ref "PHD73") (pin "4") (pinfunction "2_4") (pintype "bidirectional"))
      (node (ref "R62") (pin "1") (pinfunction "1_1") (pintype "passive"))
    )
    (net (code "177") (name "/PD74") (class "Default")
      (node (ref "IC14") (pin "9") (pinfunction "-IN_9") (pintype "input"))
      (node (ref "PHD74") (pin "3") (pinfunction "2_3") (pintype "bidirectional"))
      (node (ref "PHD74") (pin "4") (pinfunction "2_4") (pintype "bidirectional"))
      (node (ref "R58") (pin "1") (pinfunction "1_1") (pintype "passive"))
    )
    (net (code "178") (name "/PD75") (class "Default")
      (node (ref "IC24") (pin "13") (pinfunction "-IN_13") (pintype "input"))
      (node (ref "PHD75") (pin "3") (pinfunction "2_3") (pintype "bidirectional"))
      (node (ref "PHD75") (pin "4") (pinfunction "2_4") (pintype "bidirectional"))
      (node (ref "R95") (pin "1") (pinfunction "1_1") (pintype "passive"))
    )
    (net (code "179") (name "/PD76") (class "Default")
      (node (ref "IC24") (pin "9") (pinfunction "-IN_9") (pintype "input"))
      (node (ref "PHD76") (pin "3") (pinfunction "2_3") (pintype "bidirectional"))
      (node (ref "PHD76") (pin "4") (pinfunction "2_4") (pintype "bidirectional"))
      (node (ref "R84") (pin "1") (pinfunction "1_1") (pintype "passive"))
    )
    (net (code "180") (name "/PD77") (class "Default")
      (node (ref "IC5") (pin "13") (pinfunction "-IN_13") (pintype "input"))
      (node (ref "PHD77") (pin "3") (pinfunction "2_3") (pintype "bidirectional"))
      (node (ref "PHD77") (pin "4") (pinfunction "2_4") (pintype "bidirectional"))
      (node (ref "R43") (pin "1") (pinfunction "1_1") (pintype "passive"))
    )
    (net (code "181") (name "/PD78") (class "Default")
      (node (ref "IC5") (pin "9") (pinfunction "-IN_9") (pintype "input"))
      (node (ref "PHD78") (pin "3") (pinfunction "2_3") (pintype "bidirectional"))
      (node (ref "PHD78") (pin "4") (pinfunction "2_4") (pintype "bidirectional"))
      (node (ref "R33") (pin "1") (pinfunction "1_1") (pintype "passive"))
    )
    (net (code "182") (name "/PD79") (class "Default")
      (node (ref "IC15") (pin "13") (pinfunction "-IN_13") (pintype "input"))
      (node (ref "PHD79") (pin "3") (pinfunction "2_3") (pintype "bidirectional"))
      (node (ref "PHD79") (pin "4") (pinfunction "2_4") (pintype "bidirectional"))
      (node (ref "R63") (pin "1") (pinfunction "1_1") (pintype "passive"))
    )
    (net (code "183") (name "/PD80") (class "Default")
      (node (ref "IC15") (pin "9") (pinfunction "-IN_9") (pintype "input"))
      (node (ref "PHD80") (pin "3") (pinfunction "2_3") (pintype "bidirectional"))
      (node (ref "PHD80") (pin "4") (pinfunction "2_4") (pintype "bidirectional"))
      (node (ref "R56") (pin "1") (pinfunction "1_1") (pintype "passive"))
    )
    (net (code "184") (name "/PD81") (class "Default")
      (node (ref "IC22") (pin "2") (pinfunction "-IN_2") (pintype "input"))
      (node (ref "PHD81") (pin "3") (pinfunction "2_3") (pintype "bidirectional"))
      (node (ref "PHD81") (pin "4") (pinfunction "2_4") (pintype "bidirectional"))
      (node (ref "R68") (pin "1") (pinfunction "1_1") (pintype "passive"))
    )
    (net (code "185") (name "/PD82") (class "Default")
      (node (ref "IC22") (pin "6") (pinfunction "-IN_6") (pintype "input"))
      (node (ref "PHD82") (pin "3") (pinfunction "2_3") (pintype "bidirectional"))
      (node (ref "PHD82") (pin "4") (pinfunction "2_4") (pintype "bidirectional"))
      (node (ref "R79") (pin "1") (pinfunction "1_1") (pintype "passive"))
    )
    (net (code "186") (name "/PD83") (class "Default")
      (node (ref "IC3") (pin "2") (pinfunction "-IN_2") (pintype "input"))
      (node (ref "PHD83") (pin "3") (pinfunction "2_3") (pintype "bidirectional"))
      (node (ref "PHD83") (pin "4") (pinfunction "2_4") (pintype "bidirectional"))
      (node (ref "R2") (pin "1") (pinfunction "1_1") (pintype "passive"))
    )
    (net (code "187") (name "/PD84") (class "Default")
      (node (ref "IC3") (pin "6") (pinfunction "-IN_6") (pintype "input"))
      (node (ref "PHD84") (pin "3") (pinfunction "2_3") (pintype "bidirectional"))
      (node (ref "PHD84") (pin "4") (pinfunction "2_4") (pintype "bidirectional"))
      (node (ref "R17") (pin "1") (pinfunction "1_1") (pintype "passive"))
    )
    (net (code "188") (name "/PD85") (class "Default")
      (node (ref "IC9") (pin "2") (pinfunction "-IN_2") (pintype "input"))
      (node (ref "PHD85") (pin "3") (pinfunction "2_3") (pintype "bidirectional"))
      (node (ref "PHD85") (pin "4") (pinfunction "2_4") (pintype "bidirectional"))
      (node (ref "R10") (pin "1") (pinfunction "1_1") (pintype "passive"))
    )
    (net (code "189") (name "/PD86") (class "Default")
      (node (ref "IC9") (pin "6") (pinfunction "-IN_6") (pintype "input"))
      (node (ref "PHD86") (pin "3") (pinfunction "2_3") (pintype "bidirectional"))
      (node (ref "PHD86") (pin "4") (pinfunction "2_4") (pintype "bidirectional"))
      (node (ref "R21") (pin "1") (pinfunction "1_1") (pintype "passive"))
    )
    (net (code "190") (name "/PD87") (class "Default")
      (node (ref "IC21") (pin "2") (pinfunction "-IN_2") (pintype "input"))
      (node (ref "PHD87") (pin "3") (pinfunction "2_3") (pintype "bidirectional"))
      (node (ref "PHD87") (pin "4") (pinfunction "2_4") (pintype "bidirectional"))
      (node (ref "R73") (pin "1") (pinfunction "1_1") (pintype "passive"))
    )
    (net (code "191") (name "/PD88") (class "Default")
      (node (ref "IC21") (pin "6") (pinfunction "-IN_6") (pintype "input"))
      (node (ref "PHD88") (pin "3") (pinfunction "2_3") (pintype "bidirectional"))
      (node (ref "PHD88") (pin "4") (pinfunction "2_4") (pintype "bidirectional"))
      (node (ref "R81") (pin "1") (pinfunction "1_1") (pintype "passive"))
    )
    (net (code "192") (name "/PD89") (class "Default")
      (node (ref "IC22") (pin "13") (pinfunction "-IN_13") (pintype "input"))
      (node (ref "PHD89") (pin "3") (pinfunction "2_3") (pintype "bidirectional"))
      (node (ref "PHD89") (pin "4") (pinfunction "2_4") (pintype "bidirectional"))
      (node (ref "R93") (pin "1") (pinfunction "1_1") (pintype "passive"))
    )
    (net (code "193") (name "/PD90") (class "Default")
      (node (ref "IC22") (pin "9") (pinfunction "-IN_9") (pintype "input"))
      (node (ref "PHD90") (pin "3") (pinfunction "2_3") (pintype "bidirectional"))
      (node (ref "PHD90") (pin "4") (pinfunction "2_4") (pintype "bidirectional"))
      (node (ref "R88") (pin "1") (pinfunction "1_1") (pintype "passive"))
    )
    (net (code "194") (name "/PD91") (class "Default")
      (node (ref "IC3") (pin "13") (pinfunction "-IN_13") (pintype "input"))
      (node (ref "PHD91") (pin "3") (pinfunction "2_3") (pintype "bidirectional"))
      (node (ref "PHD91") (pin "4") (pinfunction "2_4") (pintype "bidirectional"))
      (node (ref "R45") (pin "1") (pinfunction "1_1") (pintype "passive"))
    )
    (net (code "195") (name "/PD92") (class "Default")
      (node (ref "IC3") (pin "9") (pinfunction "-IN_9") (pintype "input"))
      (node (ref "PHD92") (pin "3") (pinfunction "2_3") (pintype "bidirectional"))
      (node (ref "PHD92") (pin "4") (pinfunction "2_4") (pintype "bidirectional"))
      (node (ref "R34") (pin "1") (pinfunction "1_1") (pintype "passive"))
    )
    (net (code "196") (name "/PD93") (class "Default")
      (node (ref "IC9") (pin "13") (pinfunction "-IN_13") (pintype "input"))
      (node (ref "PHD93") (pin "3") (pinfunction "2_3") (pintype "bidirectional"))
      (node (ref "PHD93") (pin "4") (pinfunction "2_4") (pintype "bidirectional"))
      (node (ref "R37") (pin "1") (pinfunction "1_1") (pintype "passive"))
    )
    (net (code "197") (name "/PD94") (class "Default")
      (node (ref "IC9") (pin "9") (pinfunction "-IN_9") (pintype "input"))
      (node (ref "PHD94") (pin "3") (pinfunction "2_3") (pintype "bidirectional"))
      (node (ref "PHD94") (pin "4") (pinfunction "2_4") (pintype "bidirectional"))
      (node (ref "R28") (pin "1") (pinfunction "1_1") (pintype "passive"))
    )
    (net (code "198") (name "/PD95") (class "Default")
      (node (ref "IC21") (pin "13") (pinfunction "-IN_13") (pintype "input"))
      (node (ref "PHD95") (pin "3") (pinfunction "2_3") (pintype "bidirectional"))
      (node (ref "PHD95") (pin "4") (pinfunction "2_4") (pintype "bidirectional"))
      (node (ref "R97") (pin "1") (pinfunction "1_1") (pintype "passive"))
    )
    (net (code "199") (name "/PD96") (class "Default")
      (node (ref "IC21") (pin "9") (pinfunction "-IN_9") (pintype "input"))
      (node (ref "PHD96") (pin "3") (pinfunction "2_3") (pintype "bidirectional"))
      (node (ref "PHD96") (pin "4") (pinfunction "2_4") (pintype "bidirectional"))
      (node (ref "R89") (pin "1") (pinfunction "1_1") (pintype "passive"))
    )
    (net (code "200") (name "/S0") (class "Default")
      (node (ref "U1") (pin "10") (pinfunction "SEL0_10") (pintype "bidirectional"))
      (node (ref "U2") (pin "10") (pinfunction "SEL0_10") (pintype "bidirectional"))
      (node (ref "U3") (pin "10") (pinfunction "SEL0_10") (pintype "bidirectional"))
      (node (ref "U4") (pin "10") (pinfunction "SEL0_10") (pintype "bidirectional"))
      (node (ref "U5") (pin "10") (pinfunction "SEL0_10") (pintype "bidirectional"))
      (node (ref "U6") (pin "10") (pinfunction "SEL0_10") (pintype "bidirectional"))
      (node (ref "X2") (pin "3") (pinfunction "KL_3") (pintype "passive"))
    )
    (net (code "201") (name "/S1") (class "Default")
      (node (ref "U1") (pin "11") (pinfunction "SEL1_11") (pintype "bidirectional"))
      (node (ref "U2") (pin "11") (pinfunction "SEL1_11") (pintype "bidirectional"))
      (node (ref "U3") (pin "11") (pinfunction "SEL1_11") (pintype "bidirectional"))
      (node (ref "U4") (pin "11") (pinfunction "SEL1_11") (pintype "bidirectional"))
      (node (ref "U5") (pin "11") (pinfunction "SEL1_11") (pintype "bidirectional"))
      (node (ref "U6") (pin "11") (pinfunction "SEL1_11") (pintype "bidirectional"))
      (node (ref "X2") (pin "4") (pinfunction "KL_4") (pintype "passive"))
    )
    (net (code "202") (name "/S2") (class "Default")
      (node (ref "U1") (pin "14") (pinfunction "SEL2_14") (pintype "bidirectional"))
      (node (ref "U2") (pin "14") (pinfunction "SEL2_14") (pintype "bidirectional"))
      (node (ref "U3") (pin "14") (pinfunction "SEL2_14") (pintype "bidirectional"))
      (node (ref "U4") (pin "14") (pinfunction "SEL2_14") (pintype "bidirectional"))
      (node (ref "U5") (pin "14") (pinfunction "SEL2_14") (pintype "bidirectional"))
      (node (ref "U6") (pin "14") (pinfunction "SEL2_14") (pintype "bidirectional"))
      (node (ref "X2") (pin "1") (pinfunction "KL_1") (pintype "passive"))
    )
    (net (code "203") (name "/S3") (class "Default")
      (node (ref "U1") (pin "13") (pinfunction "SEL3_13") (pintype "bidirectional"))
      (node (ref "U2") (pin "13") (pinfunction "SEL3_13") (pintype "bidirectional"))
      (node (ref "U3") (pin "13") (pinfunction "SEL3_13") (pintype "bidirectional"))
      (node (ref "U4") (pin "13") (pinfunction "SEL3_13") (pintype "bidirectional"))
      (node (ref "U5") (pin "13") (pinfunction "SEL3_13") (pintype "bidirectional"))
      (node (ref "U6") (pin "13") (pinfunction "SEL3_13") (pintype "bidirectional"))
      (node (ref "X2") (pin "2") (pinfunction "KL_2") (pintype "passive"))
    )
    (net (code "204") (name "GND") (class "Default")
      (node (ref "C1") (pin "2") (pinfunction "2_2") (pintype "passive"))
      (node (ref "C10") (pin "2") (pinfunction "2_2") (pintype "passive"))
      (node (ref "C11") (pin "2") (pinfunction "2_2") (pintype "passive"))
      (node (ref "C12") (pin "2") (pinfunction "2_2") (pintype "passive"))
      (node (ref "C13") (pin "2") (pinfunction "2_2") (pintype "passive"))
      (node (ref "C14") (pin "2") (pinfunction "2_2") (pintype "passive"))
      (node (ref "C15") (pin "2") (pinfunction "2_2") (pintype "passive"))
      (node (ref "C16") (pin "2") (pinfunction "2_2") (pintype "passive"))
      (node (ref "C17") (pin "2") (pinfunction "2_2") (pintype "passive"))
      (node (ref "C18") (pin "2") (pinfunction "2_2") (pintype "passive"))
      (node (ref "C19") (pin "2") (pinfunction "2_2") (pintype "passive"))
      (node (ref "C2") (pin "2") (pinfunction "2_2") (pintype "passive"))
      (node (ref "C20") (pin "2") (pinfunction "2_2") (pintype "passive"))
      (node (ref "C21") (pin "2") (pinfunction "2_2") (pintype "passive"))
      (node (ref "C22") (pin "2") (pinfunction "2_2") (pintype "passive"))
      (node (ref "C23") (pin "2") (pinfunction "2_2") (pintype "passive"))
      (node (ref "C25") (pin "2") (pinfunction "2_2") (pintype "passive"))
      (node (ref "C3") (pin "2") (pinfunction "2_2") (pintype "passive"))
      (node (ref "C4") (pin "2") (pinfunction "2_2") (pintype "passive"))
      (node (ref "C5") (pin "2") (pinfunction "2_2") (pintype "passive"))
      (node (ref "C6") (pin "2") (pinfunction "2_2") (pintype "passive"))
      (node (ref "C7") (pin "2") (pinfunction "2_2") (pintype "passive"))
      (node (ref "C8") (pin "2") (pinfunction "2_2") (pintype "passive"))
      (node (ref "C9") (pin "2") (pinfunction "2_2") (pintype "passive"))
      (node (ref "IC1") (pin "10") (pinfunction "+IN_10") (pintype "input"))
      (node (ref "IC1") (pin "11") (pinfunction "V-_11") (pintype "power_in"))
      (node (ref "IC1") (pin "12") (pinfunction "+IN_12") (pintype "input"))
      (node (ref "IC1") (pin "3") (pinfunction "+IN_3") (pintype "input"))
      (node (ref "IC1") (pin "5") (pinfunction "+IN_5") (pintype "input"))
      (node (ref "IC10") (pin "10") (pinfunction "+IN_10") (pintype "input"))
      (node (ref "IC10") (pin "11") (pinfunction "V-_11") (pintype "power_in"))
      (node (ref "IC10") (pin "12") (pinfunction "+IN_12") (pintype "input"))
      (node (ref "IC10") (pin "3") (pinfunction "+IN_3") (pintype "input"))
      (node (ref "IC10") (pin "5") (pinfunction "+IN_5") (pintype "input"))
      (node (ref "IC11") (pin "10") (pinfunction "+IN_10") (pintype "input"))
      (node (ref "IC11") (pin "11") (pinfunction "V-_11") (pintype "power_in"))
      (node (ref "IC11") (pin "12") (pinfunction "+IN_12") (pintype "input"))
      (node (ref "IC11") (pin "3") (pinfunction "+IN_3") (pintype "input"))
      (node (ref "IC11") (pin "5") (pinfunction "+IN_5") (pintype "input"))
      (node (ref "IC12") (pin "10") (pinfunction "+IN_10") (pintype "input"))
      (node (ref "IC12") (pin "11") (pinfunction "V-_11") (pintype "power_in"))
      (node (ref "IC12") (pin "12") (pinfunction "+IN_12") (pintype "input"))
      (node (ref "IC12") (pin "3") (pinfunction "+IN_3") (pintype "input"))
      (node (ref "IC12") (pin "5") (pinfunction "+IN_5") (pintype "input"))
      (node (ref "IC13") (pin "10") (pinfunction "+IN_10") (pintype "input"))
      (node (ref "IC13") (pin "11") (pinfunction "V-_11") (pintype "power_in"))
      (node (ref "IC13") (pin "12") (pinfunction "+IN_12") (pintype "input"))
      (node (ref "IC13") (pin "3") (pinfunction "+IN_3") (pintype "input"))
      (node (ref "IC13") (pin "5") (pinfunction "+IN_5") (pintype "input"))
      (node (ref "IC14") (pin "10") (pinfunction "+IN_10") (pintype "input"))
      (node (ref "IC14") (pin "11") (pinfunction "V-_11") (pintype "power_in"))
      (node (ref "IC14") (pin "12") (pinfunction "+IN_12") (pintype "input"))
      (node (ref "IC14") (pin "3") (pinfunction "+IN_3") (pintype "input"))
      (node (ref "IC14") (pin "5") (pinfunction "+IN_5") (pintype "input"))
      (node (ref "IC15") (pin "10") (pinfunction "+IN_10") (pintype "input"))
      (node (ref "IC15") (pin "11") (pinfunction "V-_11") (pintype "power_in"))
      (node (ref "IC15") (pin "12") (pinfunction "+IN_12") (pintype "input"))
      (node (ref "IC15") (pin "3") (pinfunction "+IN_3") (pintype "input"))
      (node (ref "IC15") (pin "5") (pinfunction "+IN_5") (pintype "input"))
      (node (ref "IC16") (pin "10") (pinfunction "+IN_10") (pintype "input"))
      (node (ref "IC16") (pin "11") (pinfunction "V-_11") (pintype "power_in"))
      (node (ref "IC16") (pin "12") (pinfunction "+IN_12") (pintype "input"))
      (node (ref "IC16") (pin "3") (pinfunction "+IN_3") (pintype "input"))
      (node (ref "IC16") (pin "5") (pinfunction "+IN_5") (pintype "input"))
      (node (ref "IC17") (pin "10") (pinfunction "+IN_10") (pintype "input"))
      (node (ref "IC17") (pin "11") (pinfunction "V-_11") (pintype "power_in"))
      (node (ref "IC17") (pin "12") (pinfunction "+IN_12") (pintype "input"))
      (node (ref "IC17") (pin "3") (pinfunction "+IN_3") (pintype "input"))
      (node (ref "IC17") (pin "5") (pinfunction "+IN_5") (pintype "input"))
      (node (ref "IC18") (pin "10") (pinfunction "+IN_10") (pintype "input"))
      (node (ref "IC18") (pin "11") (pinfunction "V-_11") (pintype "power_in"))
      (node (ref "IC18") (pin "12") (pinfunction "+IN_12") (pintype "input"))
      (node (ref "IC18") (pin "3") (pinfunction "+IN_3") (pintype "input"))
      (node (ref "IC18") (pin "5") (pinfunction "+IN_5") (pintype "input"))
      (node (ref "IC19") (pin "10") (pinfunction "+IN_10") (pintype "input"))
      (node (ref "IC19") (pin "11") (pinfunction "V-_11") (pintype "power_in"))
      (node (ref "IC19") (pin "12") (pinfunction "+IN_12") (pintype "input"))
      (node (ref "IC19") (pin "3") (pinfunction "+IN_3") (pintype "input"))
      (node (ref "IC19") (pin "5") (pinfunction "+IN_5") (pintype "input"))
      (node (ref "IC2") (pin "10") (pinfunction "+IN_10") (pintype "input"))
      (node (ref "IC2") (pin "11") (pinfunction "V-_11") (pintype "power_in"))
      (node (ref "IC2") (pin "12") (pinfunction "+IN_12") (pintype "input"))
      (node (ref "IC2") (pin "3") (pinfunction "+IN_3") (pintype "input"))
      (node (ref "IC2") (pin "5") (pinfunction "+IN_5") (pintype "input"))
      (node (ref "IC20") (pin "10") (pinfunction "+IN_10") (pintype "input"))
      (node (ref "IC20") (pin "11") (pinfunction "V-_11") (pintype "power_in"))
      (node (ref "IC20") (pin "12") (pinfunction "+IN_12") (pintype "input"))
      (node (ref "IC20") (pin "3") (pinfunction "+IN_3") (pintype "input"))
      (node (ref "IC20") (pin "5") (pinfunction "+IN_5") (pintype "input"))
      (node (ref "IC21") (pin "10") (pinfunction "+IN_10") (pintype "input"))
      (node (ref "IC21") (pin "11") (pinfunction "V-_11") (pintype "power_in"))
      (node (ref "IC21") (pin "12") (pinfunction "+IN_12") (pintype "input"))
      (node (ref "IC21") (pin "3") (pinfunction "+IN_3") (pintype "input"))
      (node (ref "IC21") (pin "5") (pinfunction "+IN_5") (pintype "input"))
      (node (ref "IC22") (pin "10") (pinfunction "+IN_10") (pintype "input"))
      (node (ref "IC22") (pin "11") (pinfunction "V-_11") (pintype "power_in"))
      (node (ref "IC22") (pin "12") (pinfunction "+IN_12") (pintype "input"))
      (node (ref "IC22") (pin "3") (pinfunction "+IN_3") (pintype "input"))
      (node (ref "IC22") (pin "5") (pinfunction "+IN_5") (pintype "input"))
      (node (ref "IC23") (pin "10") (pinfunction "+IN_10") (pintype "input"))
      (node (ref "IC23") (pin "11") (pinfunction "V-_11") (pintype "power_in"))
      (node (ref "IC23") (pin "12") (pinfunction "+IN_12") (pintype "input"))
      (node (ref "IC23") (pin "3") (pinfunction "+IN_3") (pintype "input"))
      (node (ref "IC23") (pin "5") (pinfunction "+IN_5") (pintype "input"))
      (node (ref "IC24") (pin "10") (pinfunction "+IN_10") (pintype "input"))
      (node (ref "IC24") (pin "11") (pinfunction "V-_11") (pintype "power_in"))
      (node (ref "IC24") (pin "12") (pinfunction "+IN_12") (pintype "input"))
      (node (ref "IC24") (pin "3") (pinfunction "+IN_3") (pintype "input"))
      (node (ref "IC24") (pin "5") (pinfunction "+IN_5") (pintype "input"))
      (node (ref "IC3") (pin "10") (pinfunction "+IN_10") (pintype "input"))
      (node (ref "IC3") (pin "11") (pinfunction "V-_11") (pintype "power_in"))
      (node (ref "IC3") (pin "12") (pinfunction "+IN_12") (pintype "input"))
      (node (ref "IC3") (pin "3") (pinfunction "+IN_3") (pintype "input"))
      (node (ref "IC3") (pin "5") (pinfunction "+IN_5") (pintype "input"))
      (node (ref "IC4") (pin "10") (pinfunction "+IN_10") (pintype "input"))
      (node (ref "IC4") (pin "11") (pinfunction "V-_11") (pintype "power_in"))
      (node (ref "IC4") (pin "12") (pinfunction "+IN_12") (pintype "input"))
      (node (ref "IC4") (pin "3") (pinfunction "+IN_3") (pintype "input"))
      (node (ref "IC4") (pin "5") (pinfunction "+IN_5") (pintype "input"))
      (node (ref "IC5") (pin "10") (pinfunction "+IN_10") (pintype "input"))
      (node (ref "IC5") (pin "11") (pinfunction "V-_11") (pintype "power_in"))
      (node (ref "IC5") (pin "12") (pinfunction "+IN_12") (pintype "input"))
      (node (ref "IC5") (pin "3") (pinfunction "+IN_3") (pintype "input"))
      (node (ref "IC5") (pin "5") (pinfunction "+IN_5") (pintype "input"))
      (node (ref "IC6") (pin "10") (pinfunction "+IN_10") (pintype "input"))
      (node (ref "IC6") (pin "11") (pinfunction "V-_11") (pintype "power_in"))
      (node (ref "IC6") (pin "12") (pinfunction "+IN_12") (pintype "input"))
      (node (ref "IC6") (pin "3") (pinfunction "+IN_3") (pintype "input"))
      (node (ref "IC6") (pin "5") (pinfunction "+IN_5") (pintype "input"))
      (node (ref "IC7") (pin "10") (pinfunction "+IN_10") (pintype "input"))
      (node (ref "IC7") (pin "11") (pinfunction "V-_11") (pintype "power_in"))
      (node (ref "IC7") (pin "12") (pinfunction "+IN_12") (pintype "input"))
      (node (ref "IC7") (pin "3") (pinfunction "+IN_3") (pintype "input"))
      (node (ref "IC7") (pin "5") (pinfunction "+IN_5") (pintype "input"))
      (node (ref "IC8") (pin "10") (pinfunction "+IN_10") (pintype "input"))
      (node (ref "IC8") (pin "11") (pinfunction "V-_11") (pintype "power_in"))
      (node (ref "IC8") (pin "12") (pinfunction "+IN_12") (pintype "input"))
      (node (ref "IC8") (pin "3") (pinfunction "+IN_3") (pintype "input"))
      (node (ref "IC8") (pin "5") (pinfunction "+IN_5") (pintype "input"))
      (node (ref "IC9") (pin "10") (pinfunction "+IN_10") (pintype "input"))
      (node (ref "IC9") (pin "11") (pinfunction "V-_11") (pintype "power_in"))
      (node (ref "IC9") (pin "12") (pinfunction "+IN_12") (pintype "input"))
      (node (ref "IC9") (pin "3") (pinfunction "+IN_3") (pintype "input"))
      (node (ref "IC9") (pin "5") (pinfunction "+IN_5") (pintype "input"))
      (node (ref "PHD1") (pin "1") (pinfunction "1_1") (pintype "bidirectional"))
      (node (ref "PHD1") (pin "2") (pinfunction "1_2") (pintype "bidirectional"))
      (node (ref "PHD10") (pin "1") (pinfunction "1_1") (pintype "bidirectional"))
      (node (ref "PHD10") (pin "2") (pinfunction "1_2") (pintype "bidirectional"))
      (node (ref "PHD11") (pin "1") (pinfunction "1_1") (pintype "bidirectional"))
      (node (ref "PHD11") (pin "2") (pinfunction "1_2") (pintype "bidirectional"))
      (node (ref "PHD12") (pin "1") (pinfunction "1_1") (pintype "bidirectional"))
      (node (ref "PHD12") (pin "2") (pinfunction "1_2") (pintype "bidirectional"))
      (node (ref "PHD13") (pin "1") (pinfunction "1_1") (pintype "bidirectional"))
      (node (ref "PHD13") (pin "2") (pinfunction "1_2") (pintype "bidirectional"))
      (node (ref "PHD14") (pin "1") (pinfunction "1_1") (pintype "bidirectional"))
      (node (ref "PHD14") (pin "2") (pinfunction "1_2") (pintype "bidirectional"))
      (node (ref "PHD15") (pin "1") (pinfunction "1_1") (pintype "bidirectional"))
      (node (ref "PHD15") (pin "2") (pinfunction "1_2") (pintype "bidirectional"))
      (node (ref "PHD16") (pin "1") (pinfunction "1_1") (pintype "bidirectional"))
      (node (ref "PHD16") (pin "2") (pinfunction "1_2") (pintype "bidirectional"))
      (node (ref "PHD17") (pin "1") (pinfunction "1_1") (pintype "bidirectional"))
      (node (ref "PHD17") (pin "2") (pinfunction "1_2") (pintype "bidirectional"))
      (node (ref "PHD18") (pin "1") (pinfunction "1_1") (pintype "bidirectional"))
      (node (ref "PHD18") (pin "2") (pinfunction "1_2") (pintype "bidirectional"))
      (node (ref "PHD19") (pin "1") (pinfunction "1_1") (pintype "bidirectional"))
      (node (ref "PHD19") (pin "2") (pinfunction "1_2") (pintype "bidirectional"))
      (node (ref "PHD2") (pin "1") (pinfunction "1_1") (pintype "bidirectional"))
      (node (ref "PHD2") (pin "2") (pinfunction "1_2") (pintype "bidirectional"))
      (node (ref "PHD20") (pin "1") (pinfunction "1_1") (pintype "bidirectional"))
      (node (ref "PHD20") (pin "2") (pinfunction "1_2") (pintype "bidirectional"))
      (node (ref "PHD21") (pin "1") (pinfunction "1_1") (pintype "bidirectional"))
      (node (ref "PHD21") (pin "2") (pinfunction "1_2") (pintype "bidirectional"))
      (node (ref "PHD22") (pin "1") (pinfunction "1_1") (pintype "bidirectional"))
      (node (ref "PHD22") (pin "2") (pinfunction "1_2") (pintype "bidirectional"))
      (node (ref "PHD23") (pin "1") (pinfunction "1_1") (pintype "bidirectional"))
      (node (ref "PHD23") (pin "2") (pinfunction "1_2") (pintype "bidirectional"))
      (node (ref "PHD24") (pin "1") (pinfunction "1_1") (pintype "bidirectional"))
      (node (ref "PHD24") (pin "2") (pinfunction "1_2") (pintype "bidirectional"))
      (node (ref "PHD25") (pin "1") (pinfunction "1_1") (pintype "bidirectional"))
      (node (ref "PHD25") (pin "2") (pinfunction "1_2") (pintype "bidirectional"))
      (node (ref "PHD26") (pin "1") (pinfunction "1_1") (pintype "bidirectional"))
      (node (ref "PHD26") (pin "2") (pinfunction "1_2") (pintype "bidirectional"))
      (node (ref "PHD27") (pin "1") (pinfunction "1_1") (pintype "bidirectional"))
      (node (ref "PHD27") (pin "2") (pinfunction "1_2") (pintype "bidirectional"))
      (node (ref "PHD28") (pin "1") (pinfunction "1_1") (pintype "bidirectional"))
      (node (ref "PHD28") (pin "2") (pinfunction "1_2") (pintype "bidirectional"))
      (node (ref "PHD29") (pin "1") (pinfunction "1_1") (pintype "bidirectional"))
      (node (ref "PHD29") (pin "2") (pinfunction "1_2") (pintype "bidirectional"))
      (node (ref "PHD3") (pin "1") (pinfunction "1_1") (pintype "bidirectional"))
      (node (ref "PHD3") (pin "2") (pinfunction "1_2") (pintype "bidirectional"))
      (node (ref "PHD30") (pin "1") (pinfunction "1_1") (pintype "bidirectional"))
      (node (ref "PHD30") (pin "2") (pinfunction "1_2") (pintype "bidirectional"))
      (node (ref "PHD31") (pin "1") (pinfunction "1_1") (pintype "bidirectional"))
      (node (ref "PHD31") (pin "2") (pinfunction "1_2") (pintype "bidirectional"))
      (node (ref "PHD32") (pin "1") (pinfunction "1_1") (pintype "bidirectional"))
      (node (ref "PHD32") (pin "2") (pinfunction "1_2") (pintype "bidirectional"))
      (node (ref "PHD33") (pin "1") (pinfunction "1_1") (pintype "bidirectional"))
      (node (ref "PHD33") (pin "2") (pinfunction "1_2") (pintype "bidirectional"))
      (node (ref "PHD34") (pin "1") (pinfunction "1_1") (pintype "bidirectional"))
      (node (ref "PHD34") (pin "2") (pinfunction "1_2") (pintype "bidirectional"))
      (node (ref "PHD35") (pin "1") (pinfunction "1_1") (pintype "bidirectional"))
      (node (ref "PHD35") (pin "2") (pinfunction "1_2") (pintype "bidirectional"))
      (node (ref "PHD36") (pin "1") (pinfunction "1_1") (pintype "bidirectional"))
      (node (ref "PHD36") (pin "2") (pinfunction "1_2") (pintype "bidirectional"))
      (node (ref "PHD37") (pin "1") (pinfunction "1_1") (pintype "bidirectional"))
      (node (ref "PHD37") (pin "2") (pinfunction "1_2") (pintype "bidirectional"))
      (node (ref "PHD38") (pin "1") (pinfunction "1_1") (pintype "bidirectional"))
      (node (ref "PHD38") (pin "2") (pinfunction "1_2") (pintype "bidirectional"))
      (node (ref "PHD39") (pin "1") (pinfunction "1_1") (pintype "bidirectional"))
      (node (ref "PHD39") (pin "2") (pinfunction "1_2") (pintype "bidirectional"))
      (node (ref "PHD4") (pin "1") (pinfunction "1_1") (pintype "bidirectional"))
      (node (ref "PHD4") (pin "2") (pinfunction "1_2") (pintype "bidirectional"))
      (node (ref "PHD40") (pin "1") (pinfunction "1_1") (pintype "bidirectional"))
      (node (ref "PHD40") (pin "2") (pinfunction "1_2") (pintype "bidirectional"))
      (node (ref "PHD41") (pin "1") (pinfunction "1_1") (pintype "bidirectional"))
      (node (ref "PHD41") (pin "2") (pinfunction "1_2") (pintype "bidirectional"))
      (node (ref "PHD42") (pin "1") (pinfunction "1_1") (pintype "bidirectional"))
      (node (ref "PHD42") (pin "2") (pinfunction "1_2") (pintype "bidirectional"))
      (node (ref "PHD43") (pin "1") (pinfunction "1_1") (pintype "bidirectional"))
      (node (ref "PHD43") (pin "2") (pinfunction "1_2") (pintype "bidirectional"))
      (node (ref "PHD44") (pin "1") (pinfunction "1_1") (pintype "bidirectional"))
      (node (ref "PHD44") (pin "2") (pinfunction "1_2") (pintype "bidirectional"))
      (node (ref "PHD45") (pin "1") (pinfunction "1_1") (pintype "bidirectional"))
      (node (ref "PHD45") (pin "2") (pinfunction "1_2") (pintype "bidirectional"))
      (node (ref "PHD46") (pin "1") (pinfunction "1_1") (pintype "bidirectional"))
      (node (ref "PHD46") (pin "2") (pinfunction "1_2") (pintype "bidirectional"))
      (node (ref "PHD47") (pin "1") (pinfunction "1_1") (pintype "bidirectional"))
      (node (ref "PHD47") (pin "2") (pinfunction "1_2") (pintype "bidirectional"))
      (node (ref "PHD48") (pin "1") (pinfunction "1_1") (pintype "bidirectional"))
      (node (ref "PHD48") (pin "2") (pinfunction "1_2") (pintype "bidirectional"))
      (node (ref "PHD49") (pin "1") (pinfunction "1_1") (pintype "bidirectional"))
      (node (ref "PHD49") (pin "2") (pinfunction "1_2") (pintype "bidirectional"))
      (node (ref "PHD5") (pin "1") (pinfunction "1_1") (pintype "bidirectional"))
      (node (ref "PHD5") (pin "2") (pinfunction "1_2") (pintype "bidirectional"))
      (node (ref "PHD50") (pin "1") (pinfunction "1_1") (pintype "bidirectional"))
      (node (ref "PHD50") (pin "2") (pinfunction "1_2") (pintype "bidirectional"))
      (node (ref "PHD51") (pin "1") (pinfunction "1_1") (pintype "bidirectional"))
      (node (ref "PHD51") (pin "2") (pinfunction "1_2") (pintype "bidirectional"))
      (node (ref "PHD52") (pin "1") (pinfunction "1_1") (pintype "bidirectional"))
      (node (ref "PHD52") (pin "2") (pinfunction "1_2") (pintype "bidirectional"))
      (node (ref "PHD53") (pin "1") (pinfunction "1_1") (pintype "bidirectional"))
      (node (ref "PHD53") (pin "2") (pinfunction "1_2") (pintype "bidirectional"))
      (node (ref "PHD54") (pin "1") (pinfunction "1_1") (pintype "bidirectional"))
      (node (ref "PHD54") (pin "2") (pinfunction "1_2") (pintype "bidirectional"))
      (node (ref "PHD55") (pin "1") (pinfunction "1_1") (pintype "bidirectional"))
      (node (ref "PHD55") (pin "2") (pinfunction "1_2") (pintype "bidirectional"))
      (node (ref "PHD56") (pin "1") (pinfunction "1_1") (pintype "bidirectional"))
      (node (ref "PHD56") (pin "2") (pinfunction "1_2") (pintype "bidirectional"))
      (node (ref "PHD57") (pin "1") (pinfunction "1_1") (pintype "bidirectional"))
      (node (ref "PHD57") (pin "2") (pinfunction "1_2") (pintype "bidirectional"))
      (node (ref "PHD58") (pin "1") (pinfunction "1_1") (pintype "bidirectional"))
      (node (ref "PHD58") (pin "2") (pinfunction "1_2") (pintype "bidirectional"))
      (node (ref "PHD59") (pin "1") (pinfunction "1_1") (pintype "bidirectional"))
      (node (ref "PHD59") (pin "2") (pinfunction "1_2") (pintype "bidirectional"))
      (node (ref "PHD6") (pin "1") (pinfunction "1_1") (pintype "bidirectional"))
      (node (ref "PHD6") (pin "2") (pinfunction "1_2") (pintype "bidirectional"))
      (node (ref "PHD60") (pin "1") (pinfunction "1_1") (pintype "bidirectional"))
      (node (ref "PHD60") (pin "2") (pinfunction "1_2") (pintype "bidirectional"))
      (node (ref "PHD61") (pin "1") (pinfunction "1_1") (pintype "bidirectional"))
      (node (ref "PHD61") (pin "2") (pinfunction "1_2") (pintype "bidirectional"))
      (node (ref "PHD62") (pin "1") (pinfunction "1_1") (pintype "bidirectional"))
      (node (ref "PHD62") (pin "2") (pinfunction "1_2") (pintype "bidirectional"))
      (node (ref "PHD63") (pin "1") (pinfunction "1_1") (pintype "bidirectional"))
      (node (ref "PHD63") (pin "2") (pinfunction "1_2") (pintype "bidirectional"))
      (node (ref "PHD64") (pin "1") (pinfunction "1_1") (pintype "bidirectional"))
      (node (ref "PHD64") (pin "2") (pinfunction "1_2") (pintype "bidirectional"))
      (node (ref "PHD65") (pin "1") (pinfunction "1_1") (pintype "bidirectional"))
      (node (ref "PHD65") (pin "2") (pinfunction "1_2") (pintype "bidirectional"))
      (node (ref "PHD66") (pin "1") (pinfunction "1_1") (pintype "bidirectional"))
      (node (ref "PHD66") (pin "2") (pinfunction "1_2") (pintype "bidirectional"))
      (node (ref "PHD67") (pin "1") (pinfunction "1_1") (pintype "bidirectional"))
      (node (ref "PHD67") (pin "2") (pinfunction "1_2") (pintype "bidirectional"))
      (node (ref "PHD68") (pin "1") (pinfunction "1_1") (pintype "bidirectional"))
      (node (ref "PHD68") (pin "2") (pinfunction "1_2") (pintype "bidirectional"))
      (node (ref "PHD69") (pin "1") (pinfunction "1_1") (pintype "bidirectional"))
      (node (ref "PHD69") (pin "2") (pinfunction "1_2") (pintype "bidirectional"))
      (node (ref "PHD7") (pin "1") (pinfunction "1_1") (pintype "bidirectional"))
      (node (ref "PHD7") (pin "2") (pinfunction "1_2") (pintype "bidirectional"))
      (node (ref "PHD70") (pin "1") (pinfunction "1_1") (pintype "bidirectional"))
      (node (ref "PHD70") (pin "2") (pinfunction "1_2") (pintype "bidirectional"))
      (node (ref "PHD71") (pin "1") (pinfunction "1_1") (pintype "bidirectional"))
      (node (ref "PHD71") (pin "2") (pinfunction "1_2") (pintype "bidirectional"))
      (node (ref "PHD72") (pin "1") (pinfunction "1_1") (pintype "bidirectional"))
      (node (ref "PHD72") (pin "2") (pinfunction "1_2") (pintype "bidirectional"))
      (node (ref "PHD73") (pin "1") (pinfunction "1_1") (pintype "bidirectional"))
      (node (ref "PHD73") (pin "2") (pinfunction "1_2") (pintype "bidirectional"))
      (node (ref "PHD74") (pin "1") (pinfunction "1_1") (pintype "bidirectional"))
      (node (ref "PHD74") (pin "2") (pinfunction "1_2") (pintype "bidirectional"))
      (node (ref "PHD75") (pin "1") (pinfunction "1_1") (pintype "bidirectional"))
      (node (ref "PHD75") (pin "2") (pinfunction "1_2") (pintype "bidirectional"))
      (node (ref "PHD76") (pin "1") (pinfunction "1_1") (pintype "bidirectional"))
      (node (ref "PHD76") (pin "2") (pinfunction "1_2") (pintype "bidirectional"))
      (node (ref "PHD77") (pin "1") (pinfunction "1_1") (pintype "bidirectional"))
      (node (ref "PHD77") (pin "2") (pinfunction "1_2") (pintype "bidirectional"))
      (node (ref "PHD78") (pin "1") (pinfunction "1_1") (pintype "bidirectional"))
      (node (ref "PHD78") (pin "2") (pinfunction "1_2") (pintype "bidirectional"))
      (node (ref "PHD79") (pin "1") (pinfunction "1_1") (pintype "bidirectional"))
      (node (ref "PHD79") (pin "2") (pinfunction "1_2") (pintype "bidirectional"))
      (node (ref "PHD8") (pin "1") (pinfunction "1_1") (pintype "bidirectional"))
      (node (ref "PHD8") (pin "2") (pinfunction "1_2") (pintype "bidirectional"))
      (node (ref "PHD80") (pin "1") (pinfunction "1_1") (pintype "bidirectional"))
      (node (ref "PHD80") (pin "2") (pinfunction "1_2") (pintype "bidirectional"))
      (node (ref "PHD81") (pin "1") (pinfunction "1_1") (pintype "bidirectional"))
      (node (ref "PHD81") (pin "2") (pinfunction "1_2") (pintype "bidirectional"))
      (node (ref "PHD82") (pin "1") (pinfunction "1_1") (pintype "bidirectional"))
      (node (ref "PHD82") (pin "2") (pinfunction "1_2") (pintype "bidirectional"))
      (node (ref "PHD83") (pin "1") (pinfunction "1_1") (pintype "bidirectional"))
      (node (ref "PHD83") (pin "2") (pinfunction "1_2") (pintype "bidirectional"))
      (node (ref "PHD84") (pin "1") (pinfunction "1_1") (pintype "bidirectional"))
      (node (ref "PHD84") (pin "2") (pinfunction "1_2") (pintype "bidirectional"))
      (node (ref "PHD85") (pin "1") (pinfunction "1_1") (pintype "bidirectional"))
      (node (ref "PHD85") (pin "2") (pinfunction "1_2") (pintype "bidirectional"))
      (node (ref "PHD86") (pin "1") (pinfunction "1_1") (pintype "bidirectional"))
      (node (ref "PHD86") (pin "2") (pinfunction "1_2") (pintype "bidirectional"))
      (node (ref "PHD87") (pin "1") (pinfunction "1_1") (pintype "bidirectional"))
      (node (ref "PHD87") (pin "2") (pinfunction "1_2") (pintype "bidirectional"))
      (node (ref "PHD88") (pin "1") (pinfunction "1_1") (pintype "bidirectional"))
      (node (ref "PHD88") (pin "2") (pinfunction "1_2") (pintype "bidirectional"))
      (node (ref "PHD89") (pin "1") (pinfunction "1_1") (pintype "bidirectional"))
      (node (ref "PHD89") (pin "2") (pinfunction "1_2") (pintype "bidirectional"))
      (node (ref "PHD9") (pin "1") (pinfunction "1_1") (pintype "bidirectional"))
      (node (ref "PHD9") (pin "2") (pinfunction "1_2") (pintype "bidirectional"))
      (node (ref "PHD90") (pin "1") (pinfunction "1_1") (pintype "bidirectional"))
      (node (ref "PHD90") (pin "2") (pinfunction "1_2") (pintype "bidirectional"))
      (node (ref "PHD91") (pin "1") (pinfunction "1_1") (pintype "bidirectional"))
      (node (ref "PHD91") (pin "2") (pinfunction "1_2") (pintype "bidirectional"))
      (node (ref "PHD92") (pin "1") (pinfunction "1_1") (pintype "bidirectional"))
      (node (ref "PHD92") (pin "2") (pinfunction "1_2") (pintype "bidirectional"))
      (node (ref "PHD93") (pin "1") (pinfunction "1_1") (pintype "bidirectional"))
      (node (ref "PHD93") (pin "2") (pinfunction "1_2") (pintype "bidirectional"))
      (node (ref "PHD94") (pin "1") (pinfunction "1_1") (pintype "bidirectional"))
      (node (ref "PHD94") (pin "2") (pinfunction "1_2") (pintype "bidirectional"))
      (node (ref "PHD95") (pin "1") (pinfunction "1_1") (pintype "bidirectional"))
      (node (ref "PHD95") (pin "2") (pinfunction "1_2") (pintype "bidirectional"))
      (node (ref "PHD96") (pin "1") (pinfunction "1_1") (pintype "bidirectional"))
      (node (ref "PHD96") (pin "2") (pinfunction "1_2") (pintype "bidirectional"))
      (node (ref "U1") (pin "12") (pinfunction "GND_12") (pintype "bidirectional"))
      (node (ref "U1") (pin "15") (pinfunction "EN_15") (pintype "bidirectional"))
      (node (ref "U2") (pin "12") (pinfunction "GND_12") (pintype "bidirectional"))
      (node (ref "U2") (pin "15") (pinfunction "EN_15") (pintype "bidirectional"))
      (node (ref "U3") (pin "12") (pinfunction "GND_12") (pintype "bidirectional"))
      (node (ref "U3") (pin "15") (pinfunction "EN_15") (pintype "bidirectional"))
      (node (ref "U4") (pin "12") (pinfunction "GND_12") (pintype "bidirectional"))
      (node (ref "U4") (pin "15") (pinfunction "EN_15") (pintype "bidirectional"))
      (node (ref "U5") (pin "12") (pinfunction "GND_12") (pintype "bidirectional"))
      (node (ref "U5") (pin "15") (pinfunction "EN_15") (pintype "bidirectional"))
      (node (ref "U6") (pin "12") (pinfunction "GND_12") (pintype "bidirectional"))
      (node (ref "U6") (pin "15") (pinfunction "EN_15") (pintype "bidirectional"))
      (node (ref "X1") (pin "1") (pinfunction "KL_1") (pintype "passive"))
    )
  )
)
